# MCS4-2.net
KiCad netlist of a schematic drawn in Altium Designer
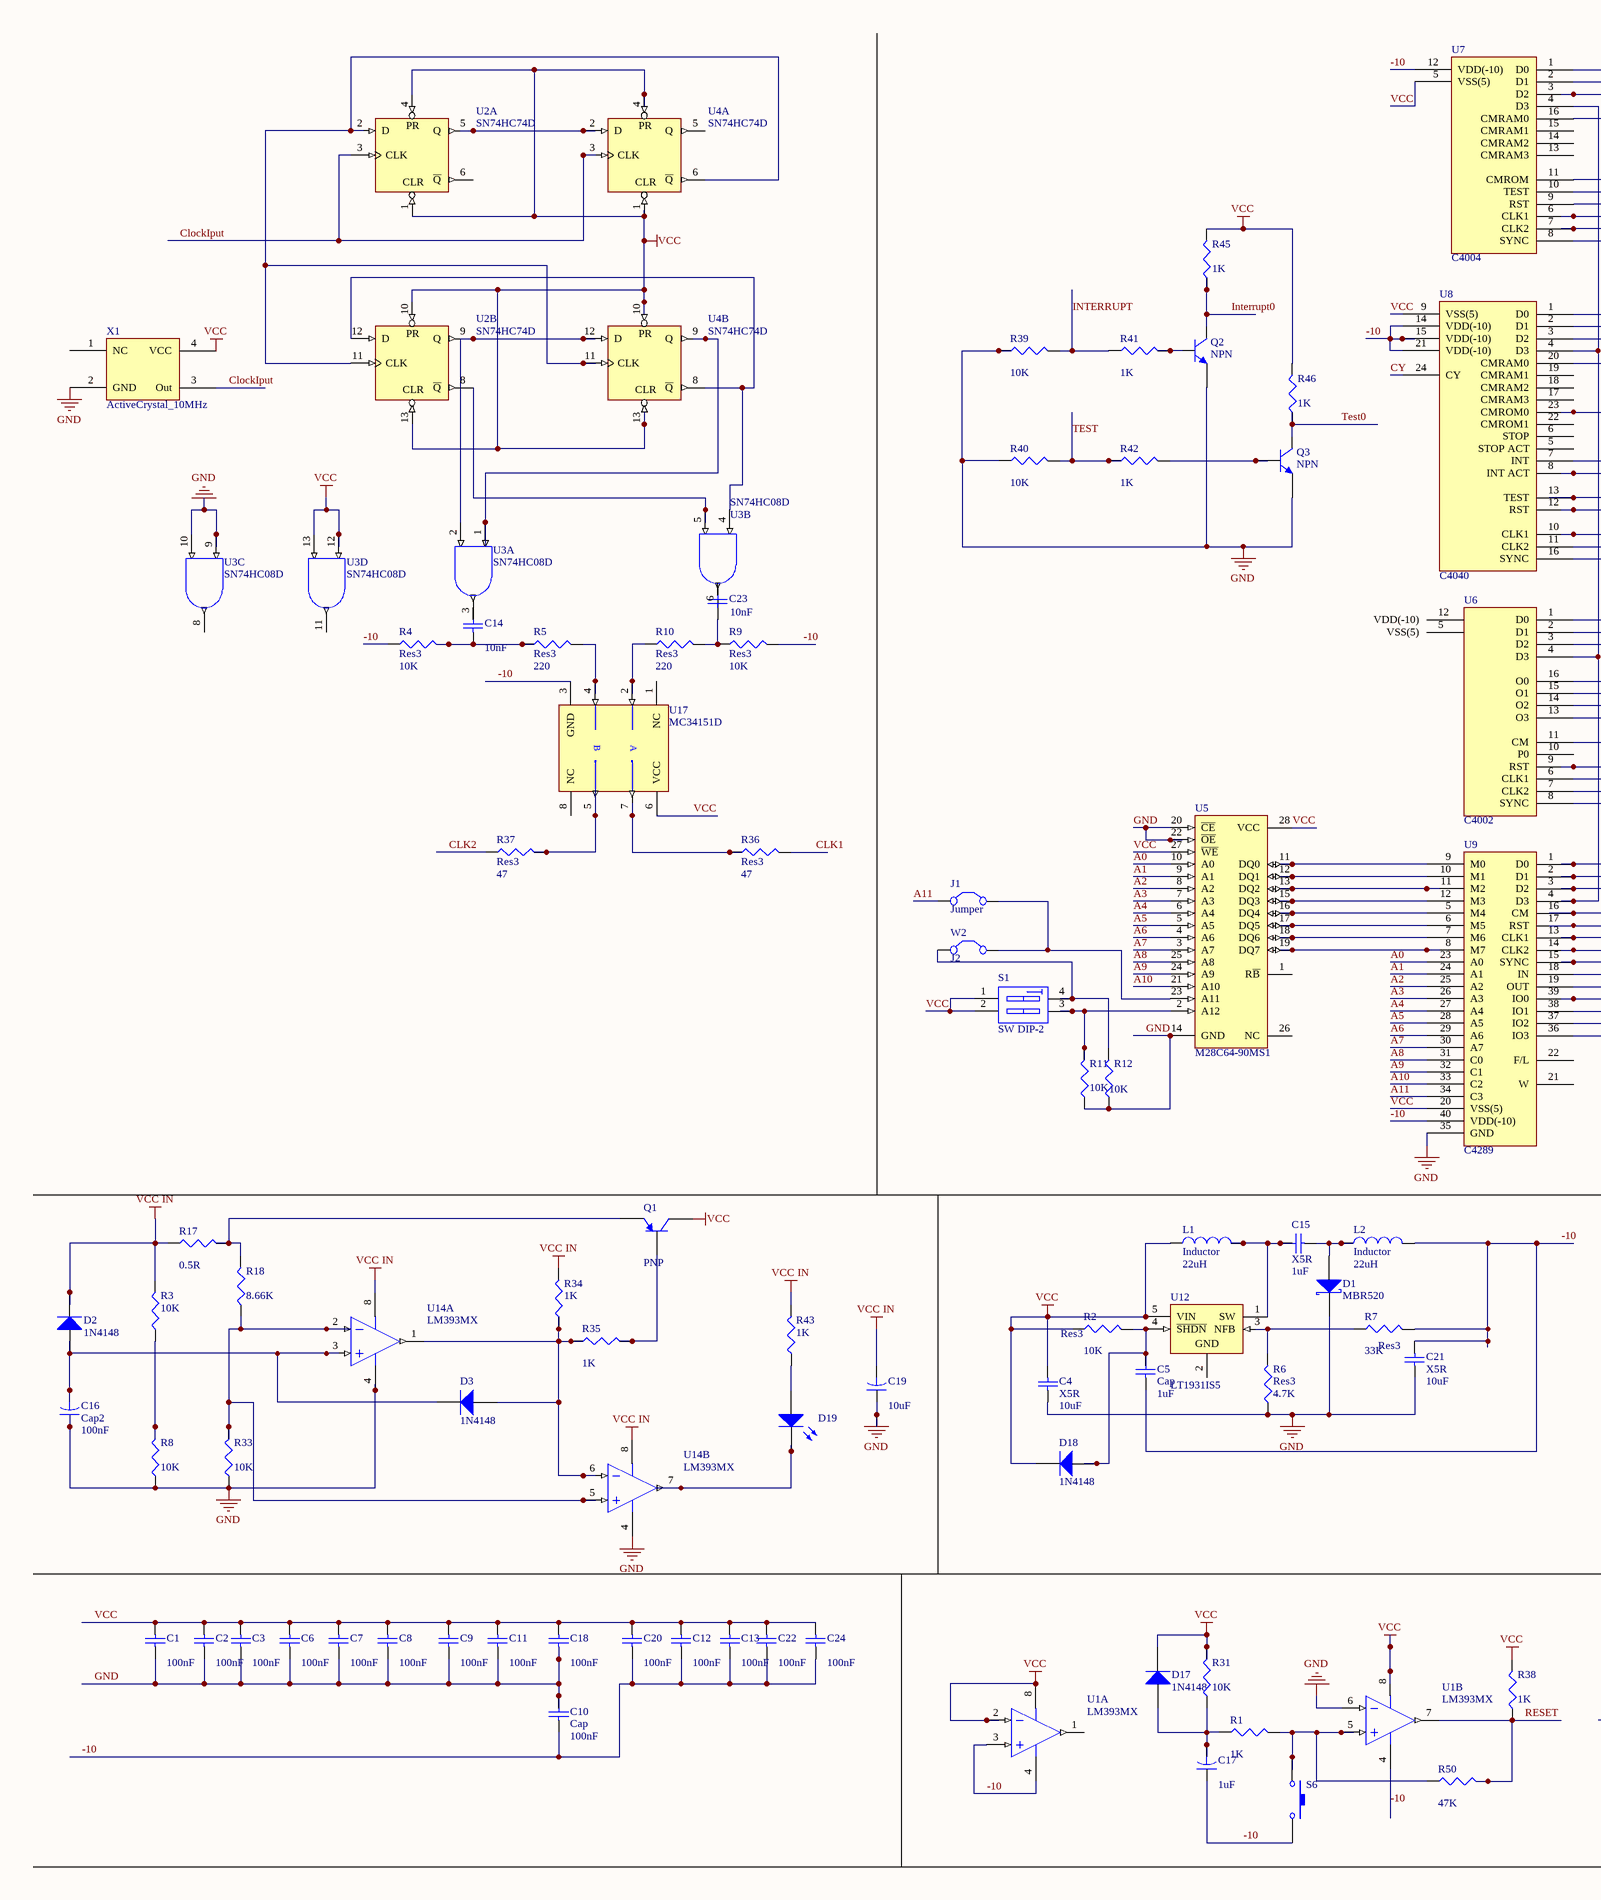
[diagram p0: MCS4-2.SchDoc, left]
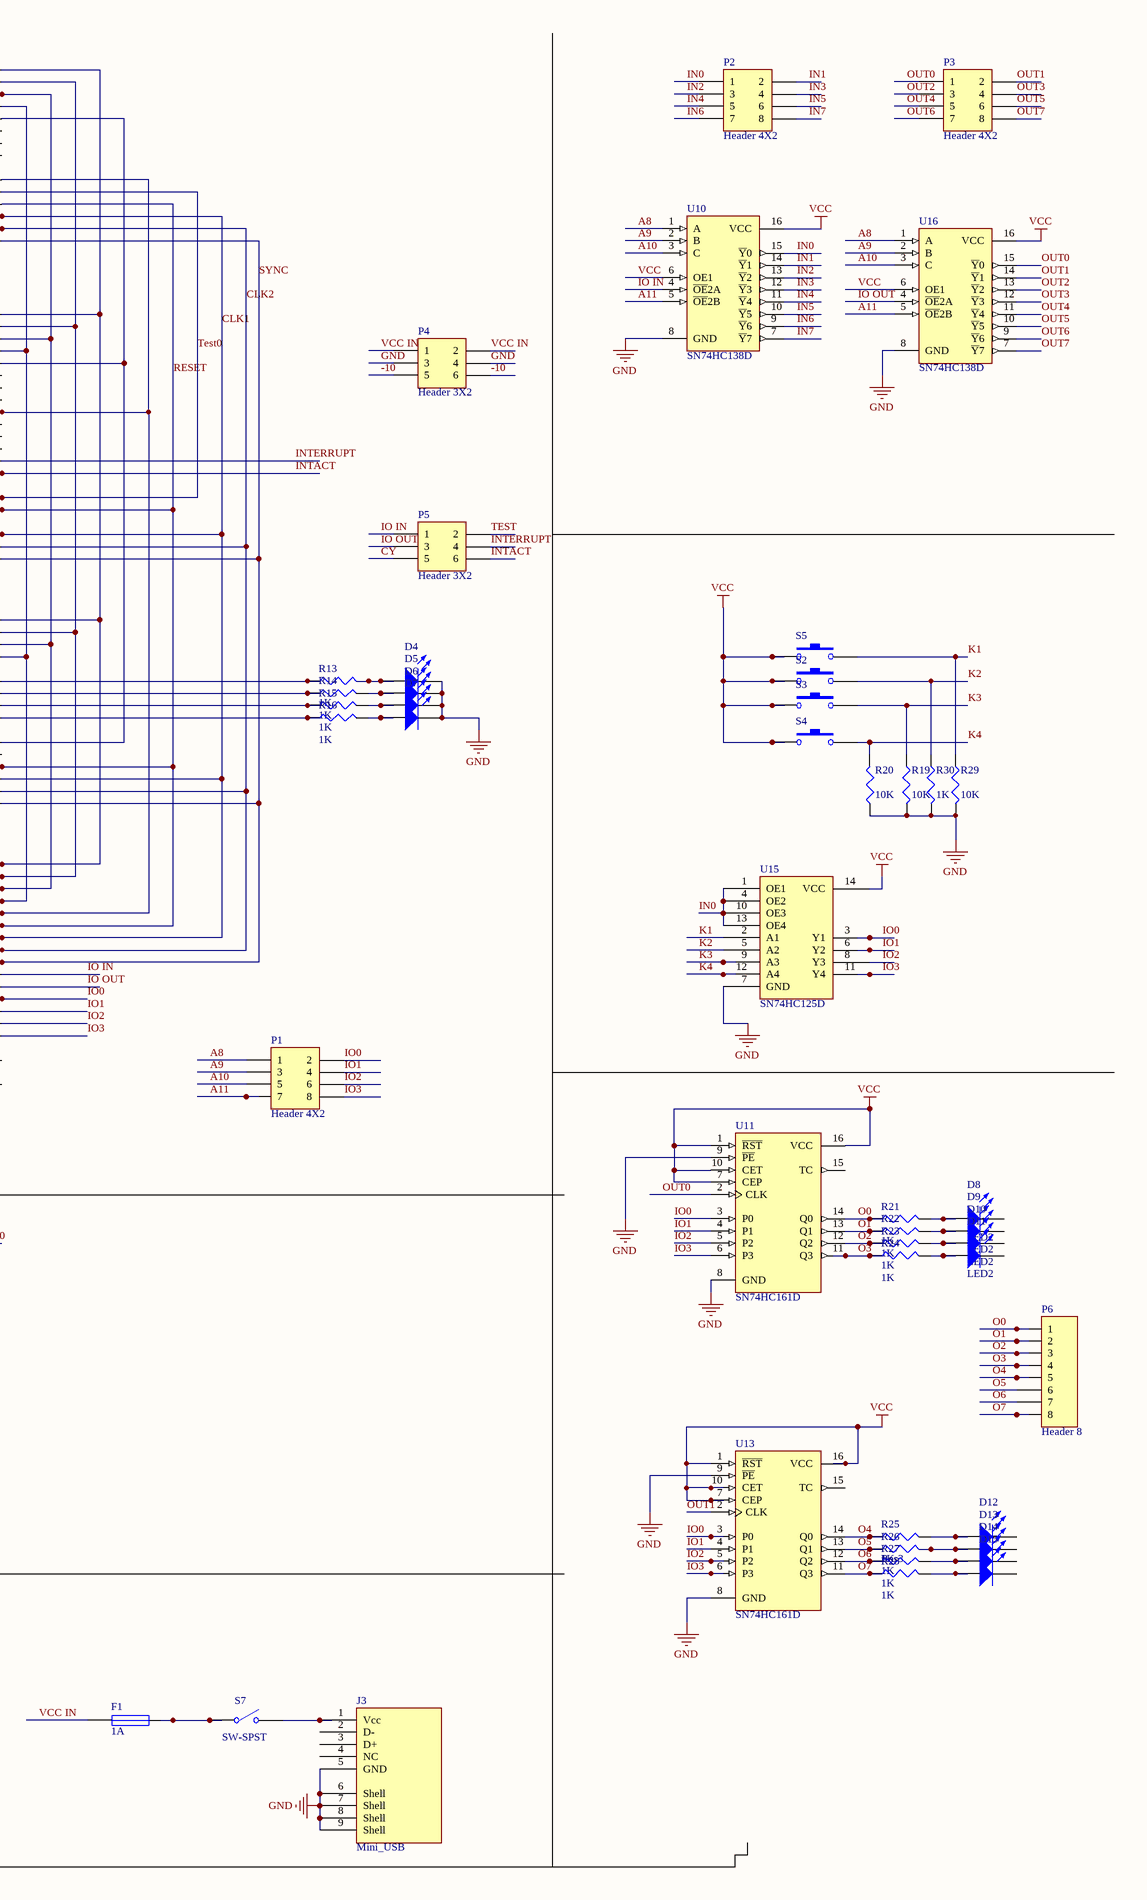
[diagram p1: MCS4-2.SchDoc, right]

(export (version "E")
  (design (tool "Eeschema 10.0.6"))
  (components
    (comp (ref "C1")
      (value "100nF")
      (footprint "RAD-0.3")
      (description "Capacitor")
      (fields (field (name "Comment") "Cap") (field (name "PUBLISHER") "Altium Limited"))
      (libsource (lib "Miscellaneous Devices") (part "Cap"))
    )
    (comp (ref "C2")
      (value "100nF")
      (footprint "RAD-0.3")
      (description "Capacitor")
      (fields (field (name "Comment") "Cap") (field (name "PUBLISHER") "Altium Limited"))
      (libsource (lib "Miscellaneous Devices") (part "Cap"))
    )
    (comp (ref "C3")
      (value "100nF")
      (footprint "RAD-0.3")
      (description "Capacitor")
      (fields (field (name "Comment") "Cap") (field (name "PUBLISHER") "Altium Limited"))
      (libsource (lib "Miscellaneous Devices") (part "Cap"))
    )
    (comp (ref "C4")
      (value "X5R")
      (footprint "RAD-0.3")
      (description "Capacitor")
      (fields (field (name "ALTIUM_VALUE") "10uF") (field (name "PUBLISHER") "Altium Limited"))
      (libsource (lib "Miscellaneous Devices") (part "Cap"))
    )
    (comp (ref "C5")
      (value "Cap")
      (footprint "RAD-0.3")
      (description "Capacitor")
      (fields (field (name "ALTIUM_VALUE") "1uF") (field (name "PUBLISHER") "Altium Limited"))
      (libsource (lib "Miscellaneous Devices") (part "Cap"))
    )
    (comp (ref "C6")
      (value "100nF")
      (footprint "RAD-0.3")
      (description "Capacitor")
      (fields (field (name "Comment") "Cap") (field (name "PUBLISHER") "Altium Limited"))
      (libsource (lib "Miscellaneous Devices") (part "Cap"))
    )
    (comp (ref "C7")
      (value "100nF")
      (footprint "RAD-0.3")
      (description "Capacitor")
      (fields (field (name "Comment") "Cap") (field (name "PUBLISHER") "Altium Limited"))
      (libsource (lib "Miscellaneous Devices") (part "Cap"))
    )
    (comp (ref "C8")
      (value "100nF")
      (footprint "RAD-0.3")
      (description "Capacitor")
      (fields (field (name "Comment") "Cap") (field (name "PUBLISHER") "Altium Limited"))
      (libsource (lib "Miscellaneous Devices") (part "Cap"))
    )
    (comp (ref "C9")
      (value "100nF")
      (footprint "RAD-0.3")
      (description "Capacitor")
      (fields (field (name "Comment") "Cap") (field (name "PUBLISHER") "Altium Limited"))
      (libsource (lib "Miscellaneous Devices") (part "Cap"))
    )
    (comp (ref "C10")
      (value "Cap")
      (footprint "RAD-0.3")
      (description "Capacitor")
      (fields (field (name "ALTIUM_VALUE") "100nF") (field (name "PUBLISHER") "Altium Limited"))
      (libsource (lib "Miscellaneous Devices") (part "Cap"))
    )
    (comp (ref "C11")
      (value "100nF")
      (footprint "RAD-0.3")
      (description "Capacitor")
      (fields (field (name "Comment") "Cap") (field (name "PUBLISHER") "Altium Limited"))
      (libsource (lib "Miscellaneous Devices") (part "Cap"))
    )
    (comp (ref "C12")
      (value "100nF")
      (footprint "RAD-0.3")
      (description "Capacitor")
      (fields (field (name "Comment") "Cap") (field (name "PUBLISHER") "Altium Limited"))
      (libsource (lib "Miscellaneous Devices") (part "Cap"))
    )
    (comp (ref "C13")
      (value "100nF")
      (footprint "RAD-0.3")
      (description "Capacitor")
      (fields (field (name "Comment") "Cap") (field (name "PUBLISHER") "Altium Limited"))
      (libsource (lib "Miscellaneous Devices") (part "Cap"))
    )
    (comp (ref "C14")
      (value "10nF")
      (footprint "RAD-0.3")
      (description "Capacitor")
      (fields (field (name "PUBLISHER") "Altium Limited"))
      (libsource (lib "Miscellaneous Devices") (part "Cap"))
    )
    (comp (ref "C15")
      (value "X5R")
      (footprint "RAD-0.3")
      (fields (field (name "ALTIUM_VALUE") "1uF") (field (name "PUBLISHER") "Altium Limited"))
      (libsource (lib "Miscellaneous Devices") (part "Cap"))
    )
    (comp (ref "C16")
      (value "Cap2")
      (footprint "CAPR5-4X5")
      (description "Capacitor")
      (fields (field (name "ALTIUM_VALUE") "100nF") (field (name "PUBLISHER") "Altium Limited"))
      (libsource (lib "Miscellaneous Devices") (part "Cap2"))
    )
    (comp (ref "C17")
      (value "1uF")
      (footprint "CAPR5-4X5")
      (description "Capacitor")
      (fields (field (name "Comment") "Cap2") (field (name "PUBLISHER") "Altium Limited"))
      (libsource (lib "Miscellaneous Devices") (part "Cap2"))
    )
    (comp (ref "C18")
      (value "100nF")
      (footprint "RAD-0.3")
      (description "Capacitor")
      (fields (field (name "Comment") "Cap") (field (name "PUBLISHER") "Altium Limited"))
      (libsource (lib "Miscellaneous Devices") (part "Cap"))
    )
    (comp (ref "C19")
      (value "10uF")
      (footprint "CAPR5-4X5")
      (description "Capacitor")
      (fields (field (name "Comment") "Cap2") (field (name "PUBLISHER") "Altium Limited"))
      (libsource (lib "Miscellaneous Devices") (part "Cap2"))
    )
    (comp (ref "C20")
      (value "100nF")
      (footprint "RAD-0.3")
      (description "Capacitor")
      (fields (field (name "Comment") "Cap") (field (name "PUBLISHER") "Altium Limited"))
      (libsource (lib "Miscellaneous Devices") (part "Cap"))
    )
    (comp (ref "C21")
      (value "X5R")
      (footprint "RAD-0.3")
      (description "Capacitor")
      (fields (field (name "ALTIUM_VALUE") "10uF") (field (name "PUBLISHER") "Altium Limited"))
      (libsource (lib "Miscellaneous Devices") (part "Cap"))
    )
    (comp (ref "C22")
      (value "100nF")
      (footprint "RAD-0.3")
      (description "Capacitor")
      (fields (field (name "Comment") "Cap") (field (name "PUBLISHER") "Altium Limited"))
      (libsource (lib "Miscellaneous Devices") (part "Cap"))
    )
    (comp (ref "C23")
      (value "10nF")
      (footprint "RAD-0.3")
      (description "Capacitor")
      (fields (field (name "Comment") "Cap") (field (name "PUBLISHER") "Altium Limited"))
      (libsource (lib "Miscellaneous Devices") (part "Cap"))
    )
    (comp (ref "C24")
      (value "100nF")
      (footprint "RAD-0.3")
      (description "Capacitor")
      (fields (field (name "Comment") "Cap") (field (name "PUBLISHER") "Altium Limited"))
      (libsource (lib "Miscellaneous Devices") (part "Cap"))
    )
    (comp (ref "D1")
      (value "MBR520")
      (footprint "SMB")
      (fields (field (name "PUBLISHER") "Altium Limited"))
      (libsource (lib "Miscellaneous Devices") (part "D Schottky"))
    )
    (comp (ref "D2")
      (value "1N4148")
      (footprint "DO-35")
      (description "High Conductance Fast Diode")
      (fields (field (name "PUBLISHER") "Altium Limited"))
      (libsource (lib "1N4148 FSC Discrete Diode") (part "1N4148"))
    )
    (comp (ref "D3")
      (value "1N4148")
      (footprint "DO-35")
      (description "High Conductance Fast Diode")
      (fields (field (name "PUBLISHER") "Altium Limited"))
      (libsource (lib "1N4148 FSC Discrete Diode") (part "1N4148"))
    )
    (comp (ref "D4")
      (value "LED2")
      (footprint "3.2X1.6X1.1")
      (description "Typical RED, GREEN, YELLOW, AMBER GaAs LED")
      (fields (field (name "PUBLISHER") "Altium Limited"))
      (libsource (lib "Miscellaneous Devices") (part "LED2"))
    )
    (comp (ref "D5")
      (value "LED2")
      (footprint "3.2X1.6X1.1")
      (description "Typical RED, GREEN, YELLOW, AMBER GaAs LED")
      (fields (field (name "PUBLISHER") "Altium Limited"))
      (libsource (lib "Miscellaneous Devices") (part "LED2"))
    )
    (comp (ref "D6")
      (value "LED2")
      (footprint "3.2X1.6X1.1")
      (description "Typical RED, GREEN, YELLOW, AMBER GaAs LED")
      (fields (field (name "PUBLISHER") "Altium Limited"))
      (libsource (lib "Miscellaneous Devices") (part "LED2"))
    )
    (comp (ref "D7")
      (value "LED2")
      (footprint "3.2X1.6X1.1")
      (description "Typical RED, GREEN, YELLOW, AMBER GaAs LED")
      (fields (field (name "PUBLISHER") "Altium Limited"))
      (libsource (lib "Miscellaneous Devices") (part "LED2"))
    )
    (comp (ref "D8")
      (value "LED2")
      (footprint "3.2X1.6X1.1")
      (description "Typical RED, GREEN, YELLOW, AMBER GaAs LED")
      (fields (field (name "PUBLISHER") "Altium Limited"))
      (libsource (lib "Miscellaneous Devices") (part "LED2"))
    )
    (comp (ref "D9")
      (value "LED2")
      (footprint "3.2X1.6X1.1")
      (description "Typical RED, GREEN, YELLOW, AMBER GaAs LED")
      (fields (field (name "PUBLISHER") "Altium Limited"))
      (libsource (lib "Miscellaneous Devices") (part "LED2"))
    )
    (comp (ref "D10")
      (value "LED2")
      (footprint "3.2X1.6X1.1")
      (description "Typical RED, GREEN, YELLOW, AMBER GaAs LED")
      (fields (field (name "PUBLISHER") "Altium Limited"))
      (libsource (lib "Miscellaneous Devices") (part "LED2"))
    )
    (comp (ref "D11")
      (value "LED2")
      (footprint "3.2X1.6X1.1")
      (description "Typical RED, GREEN, YELLOW, AMBER GaAs LED")
      (fields (field (name "PUBLISHER") "Altium Limited"))
      (libsource (lib "Miscellaneous Devices") (part "LED2"))
    )
    (comp (ref "D12")
      (value "LED2")
      (footprint "3.2X1.6X1.1")
      (description "Typical RED, GREEN, YELLOW, AMBER GaAs LED")
      (fields (field (name "PUBLISHER") "Altium Limited"))
      (libsource (lib "Miscellaneous Devices") (part "LED2"))
    )
    (comp (ref "D13")
      (value "LED2")
      (footprint "3.2X1.6X1.1")
      (description "Typical RED, GREEN, YELLOW, AMBER GaAs LED")
      (fields (field (name "PUBLISHER") "Altium Limited"))
      (libsource (lib "Miscellaneous Devices") (part "LED2"))
    )
    (comp (ref "D14")
      (value "LED2")
      (footprint "3.2X1.6X1.1")
      (description "Typical RED, GREEN, YELLOW, AMBER GaAs LED")
      (fields (field (name "PUBLISHER") "Altium Limited"))
      (libsource (lib "Miscellaneous Devices") (part "LED2"))
    )
    (comp (ref "D15")
      (value "LED2")
      (footprint "3.2X1.6X1.1")
      (description "Typical RED, GREEN, YELLOW, AMBER GaAs LED")
      (fields (field (name "PUBLISHER") "Altium Limited"))
      (libsource (lib "Miscellaneous Devices") (part "LED2"))
    )
    (comp (ref "D17")
      (value "1N4148")
      (footprint "DO-35")
      (description "High Conductance Fast Diode")
      (fields (field (name "PUBLISHER") "Altium Limited"))
      (libsource (lib "1N4148 FSC Discrete Diode") (part "1N4148"))
    )
    (comp (ref "D18")
      (value "1N4148")
      (footprint "DO-35")
      (description "High Conductance Fast Diode")
      (fields (field (name "PUBLISHER") "Altium Limited"))
      (libsource (lib "1N4148 FSC Discrete Diode") (part "1N4148"))
    )
    (comp (ref "D19")
      (value "LED2")
      (footprint "3.2X1.6X1.1")
      (description "Typical RED, GREEN, YELLOW, AMBER GaAs LED")
      (fields (field (name "PUBLISHER") "Altium Limited"))
      (libsource (lib "Miscellaneous Devices") (part "LED2"))
    )
    (comp (ref "F1")
      (value "1A")
      (footprint "PIN-W2/E2.8")
      (fields (field (name "PUBLISHER") "Altium Limited"))
      (libsource (lib "Miscellaneous Devices") (part "Fuse 1"))
    )
    (comp (ref "J1")
      (value "Jumper")
      (footprint "RAD-0.2")
      (description "Jumper Wire")
      (fields (field (name "PUBLISHER") "Altium Limited"))
      (libsource (lib "Miscellaneous Devices") (part "Jumper"))
    )
    (comp (ref "J3") (value "Mini_USB") (footprint "Mini_USB") (libsource (lib "usbmin2") (part "Mini_USB")))
    (comp (ref "L1")
      (value "Inductor")
      (footprint "INDP110102X50N")
      (fields (field (name "ALTIUM_VALUE") "22uH") (field (name "PUBLISHER") "Altium Limited"))
      (libsource (lib "Miscellaneous Devices") (part "Inductor"))
    )
    (comp (ref "L2")
      (value "Inductor")
      (footprint "INDP110102X50N")
      (fields (field (name "ALTIUM_VALUE") "22uH") (field (name "PUBLISHER") "Altium Limited"))
      (libsource (lib "Miscellaneous Devices") (part "Inductor"))
    )
    (comp (ref "P1")
      (value "Header 4X2")
      (footprint "HDR2X4")
      (description "Header, 4-Pin, Dual row")
      (fields (field (name "PUBLISHER") "Altium Limited"))
      (libsource (lib "Miscellaneous Connectors") (part "Header 4X2"))
    )
    (comp (ref "P2")
      (value "Header 4X2")
      (footprint "HDR2X4")
      (description "Header, 4-Pin, Dual row")
      (fields (field (name "PUBLISHER") "Altium Limited"))
      (libsource (lib "Miscellaneous Connectors") (part "Header 4X2"))
    )
    (comp (ref "P3")
      (value "Header 4X2")
      (footprint "HDR2X4")
      (description "Header, 4-Pin, Dual row")
      (fields (field (name "PUBLISHER") "Altium Limited"))
      (libsource (lib "Miscellaneous Connectors") (part "Header 4X2"))
    )
    (comp (ref "P4")
      (value "Header 3X2")
      (footprint "HDR2X3")
      (description "Header, 3-Pin, Dual row")
      (fields (field (name "PUBLISHER") "Altium Limited"))
      (libsource (lib "Miscellaneous Connectors") (part "Header 3X2"))
    )
    (comp (ref "P5")
      (value "Header 3X2")
      (footprint "HDR2X3")
      (description "Header, 3-Pin, Dual row")
      (fields (field (name "PUBLISHER") "Altium Limited"))
      (libsource (lib "Miscellaneous Connectors") (part "Header 3X2"))
    )
    (comp (ref "P6")
      (value "Header 8")
      (footprint "HDR1X8")
      (description "Header, 8-Pin")
      (fields (field (name "PUBLISHER") "Altium Limited"))
      (libsource (lib "Miscellaneous Connectors") (part "Header 8"))
    )
    (comp (ref "Q1")
      (value "PNP")
      (footprint "SOT-23B_N")
      (description "PNP Bipolar Transistor")
      (fields (field (name "PUBLISHER") "Altium Limited"))
      (libsource (lib "Miscellaneous Devices") (part "PNP"))
    )
    (comp (ref "Q2")
      (value "NPN")
      (footprint "TO-226-AA")
      (description "NPN Bipolar Transistor")
      (fields (field (name "PUBLISHER") "Altium Limited"))
      (libsource (lib "Miscellaneous Devices") (part "NPN"))
    )
    (comp (ref "Q3")
      (value "NPN")
      (footprint "TO-226-AA")
      (description "NPN Bipolar Transistor")
      (fields (field (name "PUBLISHER") "Altium Limited"))
      (libsource (lib "Miscellaneous Devices") (part "NPN"))
    )
    (comp (ref "R1")
      (value "1K")
      (footprint "J1-0603")
      (description "Resistor")
      (fields (field (name "Comment") "Res3") (field (name "PUBLISHER") "Altium Limited"))
      (libsource (lib "Miscellaneous Devices") (part "Res3"))
    )
    (comp (ref "R2")
      (value "Res3")
      (footprint "J1-0603")
      (description "Resistor")
      (fields (field (name "ALTIUM_VALUE") "10K") (field (name "PUBLISHER") "Altium Limited"))
      (libsource (lib "Miscellaneous Devices") (part "Res3"))
    )
    (comp (ref "R3")
      (value "10K")
      (footprint "J1-0603")
      (description "Resistor")
      (fields (field (name "Comment") "Res3") (field (name "PUBLISHER") "Altium Limited"))
      (libsource (lib "Miscellaneous Devices") (part "Res3"))
    )
    (comp (ref "R4")
      (value "Res3")
      (footprint "J1-0603")
      (description "Resistor")
      (fields (field (name "ALTIUM_VALUE") "10K") (field (name "PUBLISHER") "Altium Limited"))
      (libsource (lib "Miscellaneous Devices") (part "Res3"))
    )
    (comp (ref "R5")
      (value "Res3")
      (footprint "J1-0603")
      (description "Resistor")
      (fields (field (name "ALTIUM_VALUE") "220") (field (name "PUBLISHER") "Altium Limited"))
      (libsource (lib "Miscellaneous Devices") (part "Res3"))
    )
    (comp (ref "R6")
      (value "Res3")
      (footprint "J1-0603")
      (description "Resistor")
      (fields (field (name "ALTIUM_VALUE") "4.7K") (field (name "PUBLISHER") "Altium Limited"))
      (libsource (lib "Miscellaneous Devices") (part "Res3"))
    )
    (comp (ref "R7")
      (value "Res3")
      (footprint "J1-0603")
      (description "Resistor")
      (fields (field (name "ALTIUM_VALUE") "33K") (field (name "PUBLISHER") "Altium Limited"))
      (libsource (lib "Miscellaneous Devices") (part "Res3"))
    )
    (comp (ref "R8")
      (value "10K")
      (footprint "J1-0603")
      (description "Resistor")
      (fields (field (name "Comment") "Res3") (field (name "PUBLISHER") "Altium Limited"))
      (libsource (lib "Miscellaneous Devices") (part "Res3"))
    )
    (comp (ref "R9")
      (value "Res3")
      (footprint "J1-0603")
      (description "Resistor")
      (fields (field (name "ALTIUM_VALUE") "10K") (field (name "PUBLISHER") "Altium Limited"))
      (libsource (lib "Miscellaneous Devices") (part "Res3"))
    )
    (comp (ref "R10")
      (value "Res3")
      (footprint "J1-0603")
      (description "Resistor")
      (fields (field (name "ALTIUM_VALUE") "220") (field (name "PUBLISHER") "Altium Limited"))
      (libsource (lib "Miscellaneous Devices") (part "Res3"))
    )
    (comp (ref "R11")
      (value "10K")
      (footprint "J1-0603")
      (description "Resistor")
      (fields (field (name "Comment") "Res3") (field (name "PUBLISHER") "Altium Limited"))
      (libsource (lib "Miscellaneous Devices") (part "Res3"))
    )
    (comp (ref "R12")
      (value "10K")
      (footprint "J1-0603")
      (description "Resistor")
      (fields (field (name "Comment") "Res3") (field (name "PUBLISHER") "Altium Limited"))
      (libsource (lib "Miscellaneous Devices") (part "Res3"))
    )
    (comp (ref "R13")
      (value "1K")
      (footprint "J1-0603")
      (description "Resistor")
      (fields (field (name "Comment") "Res3") (field (name "PUBLISHER") "Altium Limited"))
      (libsource (lib "Miscellaneous Devices") (part "Res3"))
    )
    (comp (ref "R14")
      (value "1K")
      (footprint "J1-0603")
      (description "Resistor")
      (fields (field (name "Comment") "Res3") (field (name "PUBLISHER") "Altium Limited"))
      (libsource (lib "Miscellaneous Devices") (part "Res3"))
    )
    (comp (ref "R15")
      (value "1K")
      (footprint "J1-0603")
      (description "Resistor")
      (fields (field (name "Comment") "Res3") (field (name "PUBLISHER") "Altium Limited"))
      (libsource (lib "Miscellaneous Devices") (part "Res3"))
    )
    (comp (ref "R16")
      (value "1K")
      (footprint "J1-0603")
      (description "Resistor")
      (fields (field (name "Comment") "Res3") (field (name "PUBLISHER") "Altium Limited"))
      (libsource (lib "Miscellaneous Devices") (part "Res3"))
    )
    (comp (ref "R17")
      (value "0.5R")
      (footprint "J1-0603")
      (description "Resistor")
      (fields (field (name "Comment") "Res3") (field (name "PUBLISHER") "Altium Limited"))
      (libsource (lib "Miscellaneous Devices") (part "Res3"))
    )
    (comp (ref "R18")
      (value "8.66K")
      (footprint "J1-0603")
      (description "Resistor")
      (fields (field (name "Comment") "Res3") (field (name "PUBLISHER") "Altium Limited"))
      (libsource (lib "Miscellaneous Devices") (part "Res3"))
    )
    (comp (ref "R19")
      (value "10K")
      (footprint "J1-0603")
      (description "Resistor")
      (fields (field (name "Comment") "Res3") (field (name "PUBLISHER") "Altium Limited"))
      (libsource (lib "Miscellaneous Devices") (part "Res3"))
    )
    (comp (ref "R20")
      (value "10K")
      (footprint "J1-0603")
      (description "Resistor")
      (fields (field (name "Comment") "Res3") (field (name "PUBLISHER") "Altium Limited"))
      (libsource (lib "Miscellaneous Devices") (part "Res3"))
    )
    (comp (ref "R21")
      (value "1K")
      (footprint "J1-0603")
      (description "Resistor")
      (fields (field (name "Comment") "Res3") (field (name "PUBLISHER") "Altium Limited"))
      (libsource (lib "Miscellaneous Devices") (part "Res3"))
    )
    (comp (ref "R22")
      (value "1K")
      (footprint "J1-0603")
      (description "Resistor")
      (fields (field (name "Comment") "Res3") (field (name "PUBLISHER") "Altium Limited"))
      (libsource (lib "Miscellaneous Devices") (part "Res3"))
    )
    (comp (ref "R23")
      (value "1K")
      (footprint "J1-0603")
      (description "Resistor")
      (fields (field (name "Comment") "Res3") (field (name "PUBLISHER") "Altium Limited"))
      (libsource (lib "Miscellaneous Devices") (part "Res3"))
    )
    (comp (ref "R24")
      (value "1K")
      (footprint "J1-0603")
      (description "Resistor")
      (fields (field (name "Comment") "Res3") (field (name "PUBLISHER") "Altium Limited"))
      (libsource (lib "Miscellaneous Devices") (part "Res3"))
    )
    (comp (ref "R25")
      (value "1K")
      (footprint "J1-0603")
      (description "Resistor")
      (fields (field (name "Comment") "Res3") (field (name "PUBLISHER") "Altium Limited"))
      (libsource (lib "Miscellaneous Devices") (part "Res3"))
    )
    (comp (ref "R26")
      (value "Res3")
      (footprint "J1-0603")
      (description "Resistor")
      (fields (field (name "ALTIUM_VALUE") "1K") (field (name "PUBLISHER") "Altium Limited"))
      (libsource (lib "Miscellaneous Devices") (part "Res3"))
    )
    (comp (ref "R27")
      (value "1K")
      (footprint "J1-0603")
      (description "Resistor")
      (fields (field (name "Comment") "Res3") (field (name "PUBLISHER") "Altium Limited"))
      (libsource (lib "Miscellaneous Devices") (part "Res3"))
    )
    (comp (ref "R28")
      (value "1K")
      (footprint "J1-0603")
      (description "Resistor")
      (fields (field (name "Comment") "Res3") (field (name "PUBLISHER") "Altium Limited"))
      (libsource (lib "Miscellaneous Devices") (part "Res3"))
    )
    (comp (ref "R29")
      (value "10K")
      (footprint "J1-0603")
      (description "Resistor")
      (fields (field (name "Comment") "Res3") (field (name "PUBLISHER") "Altium Limited"))
      (libsource (lib "Miscellaneous Devices") (part "Res3"))
    )
    (comp (ref "R30")
      (value "1K")
      (footprint "J1-0603")
      (description "Resistor")
      (fields (field (name "Comment") "Res3") (field (name "PUBLISHER") "Altium Limited"))
      (libsource (lib "Miscellaneous Devices") (part "Res3"))
    )
    (comp (ref "R31")
      (value "10K")
      (footprint "J1-0603")
      (description "Resistor")
      (fields (field (name "Comment") "Res3") (field (name "PUBLISHER") "Altium Limited"))
      (libsource (lib "Miscellaneous Devices") (part "Res3"))
    )
    (comp (ref "R33")
      (value "10K")
      (footprint "J1-0603")
      (description "Resistor")
      (fields (field (name "Comment") "Res3") (field (name "PUBLISHER") "Altium Limited"))
      (libsource (lib "Miscellaneous Devices") (part "Res3"))
    )
    (comp (ref "R34")
      (value "1K")
      (footprint "J1-0603")
      (description "Resistor")
      (fields (field (name "Comment") "Res3") (field (name "PUBLISHER") "Altium Limited"))
      (libsource (lib "Miscellaneous Devices") (part "Res3"))
    )
    (comp (ref "R35")
      (value "1K")
      (footprint "J1-0603")
      (description "Resistor")
      (fields (field (name "Comment") "Res3") (field (name "PUBLISHER") "Altium Limited"))
      (libsource (lib "Miscellaneous Devices") (part "Res3"))
    )
    (comp (ref "R36")
      (value "Res3")
      (footprint "J1-0603")
      (description "Resistor")
      (fields (field (name "ALTIUM_VALUE") "47") (field (name "PUBLISHER") "Altium Limited"))
      (libsource (lib "Miscellaneous Devices") (part "Res3"))
    )
    (comp (ref "R37")
      (value "Res3")
      (footprint "J1-0603")
      (description "Resistor")
      (fields (field (name "ALTIUM_VALUE") "47") (field (name "PUBLISHER") "Altium Limited"))
      (libsource (lib "Miscellaneous Devices") (part "Res3"))
    )
    (comp (ref "R38")
      (value "1K")
      (footprint "J1-0603")
      (description "Resistor")
      (fields (field (name "Comment") "Res3") (field (name "PUBLISHER") "Altium Limited"))
      (libsource (lib "Miscellaneous Devices") (part "Res3"))
    )
    (comp (ref "R39")
      (value "10K")
      (footprint "J1-0603")
      (description "Resistor")
      (fields (field (name "Comment") "Res3") (field (name "PUBLISHER") "Altium Limited"))
      (libsource (lib "Miscellaneous Devices") (part "Res3"))
    )
    (comp (ref "R40")
      (value "10K")
      (footprint "J1-0603")
      (description "Resistor")
      (fields (field (name "Comment") "Res3") (field (name "PUBLISHER") "Altium Limited"))
      (libsource (lib "Miscellaneous Devices") (part "Res3"))
    )
    (comp (ref "R41")
      (value "1K")
      (footprint "J1-0603")
      (description "Resistor")
      (fields (field (name "Comment") "Res3") (field (name "PUBLISHER") "Altium Limited"))
      (libsource (lib "Miscellaneous Devices") (part "Res3"))
    )
    (comp (ref "R42")
      (value "1K")
      (footprint "J1-0603")
      (description "Resistor")
      (fields (field (name "Comment") "Res3") (field (name "PUBLISHER") "Altium Limited"))
      (libsource (lib "Miscellaneous Devices") (part "Res3"))
    )
    (comp (ref "R43")
      (value "1K")
      (footprint "J1-0603")
      (description "Resistor")
      (fields (field (name "Comment") "Res3") (field (name "PUBLISHER") "Altium Limited"))
      (libsource (lib "Miscellaneous Devices") (part "Res3"))
    )
    (comp (ref "R45")
      (value "1K")
      (footprint "J1-0603")
      (description "Resistor")
      (fields (field (name "Comment") "Res3") (field (name "PUBLISHER") "Altium Limited"))
      (libsource (lib "Miscellaneous Devices") (part "Res3"))
    )
    (comp (ref "R46")
      (value "1K")
      (footprint "J1-0603")
      (description "Resistor")
      (fields (field (name "Comment") "Res3") (field (name "PUBLISHER") "Altium Limited"))
      (libsource (lib "Miscellaneous Devices") (part "Res3"))
    )
    (comp (ref "R50")
      (value "47K")
      (footprint "J1-0603")
      (description "Resistor")
      (fields (field (name "Comment") "Res3") (field (name "PUBLISHER") "Altium Limited"))
      (libsource (lib "Miscellaneous Devices") (part "Res3"))
    )
    (comp (ref "S1")
      (value "SW DIP-2")
      (footprint "DIP-4")
      (description "DIP Switch, 2 Position, SPST")
      (fields (field (name "PUBLISHER") "Altium Limited"))
      (libsource (lib "Miscellaneous Devices") (part "SW DIP-2"))
    )
    (comp (ref "S2")
      (value "SW-PB")
      (footprint "SPST-2")
      (description "Switch")
      (fields (field (name "PUBLISHER") "Altium Limited"))
      (libsource (lib "Miscellaneous Devices") (part "SW-PB"))
    )
    (comp (ref "S3")
      (value "SW-PB")
      (footprint "SPST-2")
      (description "Switch")
      (fields (field (name "PUBLISHER") "Altium Limited"))
      (libsource (lib "Miscellaneous Devices") (part "SW-PB"))
    )
    (comp (ref "S4")
      (value "SW-PB")
      (footprint "SPST-2")
      (description "Switch")
      (fields (field (name "PUBLISHER") "Altium Limited"))
      (libsource (lib "Miscellaneous Devices") (part "SW-PB"))
    )
    (comp (ref "S5")
      (value "SW-PB")
      (footprint "SPST-2")
      (description "Switch")
      (fields (field (name "PUBLISHER") "Altium Limited"))
      (libsource (lib "Miscellaneous Devices") (part "SW-PB"))
    )
    (comp (ref "S6")
      (value "SW-PB")
      (footprint "SPST-2")
      (description "Switch")
      (fields (field (name "PUBLISHER") "Altium Limited"))
      (libsource (lib "Miscellaneous Devices") (part "SW-PB"))
    )
    (comp (ref "S7")
      (value "SW-SPST")
      (footprint "SPST-2")
      (description "Single-Pole, Single-Throw Switch")
      (fields (field (name "PUBLISHER") "Altium Limited"))
      (libsource (lib "Miscellaneous Devices") (part "SW-SPST"))
    )
    (comp (ref "U1")
      (value "LM393MX")
      (footprint "M08A_N")
      (description "Low Power Low Offset Voltage Dual Comparator")
      (fields
        (field (name "MANUFACTURER") "National Semiconductor")
        (field (name "DIGIKEYPARTNUMBER") "LM393MXCT-ND")
        (field (name "PUBLISHER") "Altium Limited")
      )
      (libsource (lib "LM393MX NSC Comparator") (part "LM393MX"))
    )
    (comp (ref "U2")
      (value "SN74HC74D")
      (footprint "D014_N")
      (description "Dual D-Type Positive-Edge-Triggered Flip-Flop with Clear and Preset")
      (fields (field (name "PUBLISHER") "Altium Limited"))
      (libsource (lib "SN74HC74DTI Logic Flip-Flop") (part "SN74HC74D"))
    )
    (comp (ref "U3")
      (value "SN74HC08D")
      (footprint "D014_N")
      (description "Quadruple 2-Input Positive-AND Gate")
      (fields (field (name "PUBLISHER") "Altium Limited"))
      (libsource (lib "SN74HC08DTI Logic Gate 2") (part "SN74HC08D"))
    )
    (comp (ref "U4")
      (value "SN74HC74D")
      (footprint "D014_N")
      (description "Dual D-Type Positive-Edge-Triggered Flip-Flop with Clear and Preset")
      (fields (field (name "PUBLISHER") "Altium Limited"))
      (libsource (lib "SN74HC74DTI Logic Flip-Flop") (part "SN74HC74D"))
    )
    (comp (ref "U5")
      (value "M28C64-90MS1")
      (footprint "SO28_N")
      (description "64 Kbit (8K x 8) Parallel EEPROM with Software Data Protection")
      (fields (field (name "PUBLISHER") "Altium Limited"))
      (libsource (lib "M28C64 ST Memory EEPROM Parallel") (part "M28C64-90MS1"))
    )
    (comp (ref "U6") (value "C4002") (footprint "P4002") (libsource (lib "C4002") (part "C4002")))
    (comp (ref "U7") (value "C4004") (footprint "P4004") (libsource (lib "C4004") (part "C4004")))
    (comp (ref "U8") (value "C4040") (footprint "P4040") (libsource (lib "C4040") (part "C4040")))
    (comp (ref "U9") (value "C4289") (footprint "C4289") (libsource (lib "C4289") (part "C4289")))
    (comp (ref "U10")
      (value "SN74HC138D")
      (footprint "D016_N")
      (description "3-Line to 8-Line Decoder / Demultiplexer")
      (fields (field (name "PUBLISHER") "Altium Limited"))
      (libsource (lib "SN74HC138DTI Logic Decoder Demux") (part "SN74HC138D"))
    )
    (comp (ref "U11")
      (value "SN74HC161D")
      (footprint "D016_N")
      (description "4-Bit Synchronous Binary Counter")
      (fields (field (name "PUBLISHER") "Altium Limited"))
      (libsource (lib "SN74HC161DTI Logic Counter") (part "SN74HC161D"))
    )
    (comp (ref "U12")
      (value "LT1931IS5")
      (footprint "S5-T_N")
      (description "1.2MHz Inverting Current Mode DC/DC Converter")
      (fields (field (name "PUBLISHER") "Altium Limited"))
      (libsource (lib "LT1931IS5LT Power Mgt DC-DC Converter") (part "LT1931IS5"))
    )
    (comp (ref "U13")
      (value "SN74HC161D")
      (footprint "D016_N")
      (description "4-Bit Synchronous Binary Counter")
      (fields (field (name "PUBLISHER") "Altium Limited"))
      (libsource (lib "SN74HC161DTI Logic Counter") (part "SN74HC161D"))
    )
    (comp (ref "U14")
      (value "LM393MX")
      (footprint "M08A_N")
      (description "Low Power Low Offset Voltage Dual Comparator")
      (fields
        (field (name "MANUFACTURER") "National Semiconductor")
        (field (name "DIGIKEYPARTNUMBER") "LM393MXCT-ND")
        (field (name "PUBLISHER") "Altium Limited")
      )
      (libsource (lib "LM393MX NSC Comparator") (part "LM393MX"))
    )
    (comp (ref "U15")
      (value "SN74HC125D")
      (footprint "SN74HC125D")
      (description "U15")
      (libsource (lib "SN74HC125D") (part "SN74HC125D"))
    )
    (comp (ref "U16")
      (value "SN74HC138D")
      (footprint "D016_N")
      (description "3-Line to 8-Line Decoder / Demultiplexer")
      (fields (field (name "PUBLISHER") "Altium Limited"))
      (libsource (lib "SN74HC138DTI Logic Decoder Demux") (part "SN74HC138D"))
    )
    (comp (ref "U17")
      (value "MC34151D")
      (footprint "751-06_N")
      (description "High Speed Dual MOSFET Driver")
      (fields (field (name "PUBLISHER") "Altium Limited"))
      (libsource (lib "MC3415DMotorola Interface MOSFET Driver") (part "MC34151D"))
    )
    (comp (ref "W2")
      (value "J2")
      (footprint "RAD-0.2")
      (description "Jumper Wire")
      (fields (field (name "PUBLISHER") "Altium Limited"))
      (libsource (lib "Miscellaneous Devices") (part "Jumper"))
    )
    (comp (ref "X1")
      (value "ActiveCrystal_10MHz")
      (footprint "ActiveCrystal_10MHz_7050")
      (libsource (lib "ActiveCrystal_10MHz") (part "ActiveCrystal_10MHz"))
    )
  )
  (nets
    (net (code "1") (name "/-10") (class "Default")
      (node (ref "C10") (pin "1") (pinfunction "1_1") (pintype "passive"))
      (node (ref "C12") (pin "1") (pinfunction "1_1") (pintype "passive"))
      (node (ref "C13") (pin "1") (pinfunction "1_1") (pintype "passive"))
      (node (ref "C17") (pin "1") (pinfunction "1_1") (pintype "passive"))
      (node (ref "C20") (pin "1") (pinfunction "1_1") (pintype "passive"))
      (node (ref "C21") (pin "2") (pinfunction "2_2") (pintype "passive"))
      (node (ref "C22") (pin "1") (pinfunction "1_1") (pintype "passive"))
      (node (ref "C24") (pin "1") (pinfunction "1_1") (pintype "passive"))
      (node (ref "C5") (pin "1") (pinfunction "1_1") (pintype "passive"))
      (node (ref "L2") (pin "2") (pinfunction "2_2") (pintype "passive"))
      (node (ref "P4") (pin "5") (pinfunction "5_5") (pintype "passive"))
      (node (ref "P4") (pin "6") (pinfunction "6_6") (pintype "passive"))
      (node (ref "R4") (pin "1") (pinfunction "1_1") (pintype "passive"))
      (node (ref "R7") (pin "2") (pinfunction "2_2") (pintype "passive"))
      (node (ref "R9") (pin "2") (pinfunction "2_2") (pintype "passive"))
      (node (ref "S6") (pin "2") (pinfunction "2_2") (pintype "passive"))
      (node (ref "U1") (pin "3") (pinfunction "INA+_3") (pintype "input"))
      (node (ref "U1") (pin "4") (pinfunction "GND_4") (pintype "power_in"))
      (node (ref "U17") (pin "3") (pinfunction "GND_3") (pintype "power_in"))
      (node (ref "U7") (pin "12") (pinfunction "VDD(-10)_12") (pintype "passive"))
      (node (ref "U8") (pin "14") (pinfunction "VDD(-10)_14") (pintype "passive"))
      (node (ref "U8") (pin "15") (pinfunction "VDD(-10)_15") (pintype "passive"))
      (node (ref "U8") (pin "21") (pinfunction "VDD(-10)_21") (pintype "passive"))
      (node (ref "U9") (pin "40") (pinfunction "VDD(-10)_40") (pintype "passive"))
    )
    (net (code "2") (name "/A0") (class "Default")
      (node (ref "U5") (pin "10") (pinfunction "A0_10") (pintype "input"))
      (node (ref "U9") (pin "23") (pinfunction "A0_23") (pintype "passive"))
    )
    (net (code "3") (name "/A1") (class "Default")
      (node (ref "U5") (pin "9") (pinfunction "A1_9") (pintype "input"))
      (node (ref "U9") (pin "24") (pinfunction "A1_24") (pintype "passive"))
    )
    (net (code "4") (name "/A2") (class "Default")
      (node (ref "U5") (pin "8") (pinfunction "A2_8") (pintype "input"))
      (node (ref "U9") (pin "25") (pinfunction "A2_25") (pintype "passive"))
    )
    (net (code "5") (name "/A3") (class "Default")
      (node (ref "U5") (pin "7") (pinfunction "A3_7") (pintype "input"))
      (node (ref "U9") (pin "26") (pinfunction "A3_26") (pintype "passive"))
    )
    (net (code "6") (name "/A4") (class "Default")
      (node (ref "U5") (pin "6") (pinfunction "A4_6") (pintype "input"))
      (node (ref "U9") (pin "27") (pinfunction "A4_27") (pintype "passive"))
    )
    (net (code "7") (name "/A5") (class "Default")
      (node (ref "U5") (pin "5") (pinfunction "A5_5") (pintype "input"))
      (node (ref "U9") (pin "28") (pinfunction "A5_28") (pintype "passive"))
    )
    (net (code "8") (name "/A6") (class "Default")
      (node (ref "U5") (pin "4") (pinfunction "A6_4") (pintype "input"))
      (node (ref "U9") (pin "29") (pinfunction "A6_29") (pintype "passive"))
    )
    (net (code "9") (name "/A7") (class "Default")
      (node (ref "U5") (pin "3") (pinfunction "A7_3") (pintype "input"))
      (node (ref "U9") (pin "30") (pinfunction "A7_30") (pintype "passive"))
    )
    (net (code "10") (name "/A8") (class "Default")
      (node (ref "P1") (pin "1") (pinfunction "1_1") (pintype "passive"))
      (node (ref "U10") (pin "1") (pinfunction "A_1") (pintype "input"))
      (node (ref "U16") (pin "1") (pinfunction "A_1") (pintype "input"))
      (node (ref "U5") (pin "25") (pinfunction "A8_25") (pintype "input"))
      (node (ref "U9") (pin "31") (pinfunction "C0_31") (pintype "passive"))
    )
    (net (code "11") (name "/A9") (class "Default")
      (node (ref "P1") (pin "3") (pinfunction "3_3") (pintype "passive"))
      (node (ref "U10") (pin "2") (pinfunction "B_2") (pintype "input"))
      (node (ref "U16") (pin "2") (pinfunction "B_2") (pintype "input"))
      (node (ref "U5") (pin "24") (pinfunction "A9_24") (pintype "input"))
      (node (ref "U9") (pin "32") (pinfunction "C1_32") (pintype "passive"))
    )
    (net (code "12") (name "/A10") (class "Default")
      (node (ref "P1") (pin "5") (pinfunction "5_5") (pintype "passive"))
      (node (ref "U10") (pin "3") (pinfunction "C_3") (pintype "input"))
      (node (ref "U16") (pin "3") (pinfunction "C_3") (pintype "input"))
      (node (ref "U5") (pin "21") (pinfunction "A10_21") (pintype "input"))
      (node (ref "U9") (pin "33") (pinfunction "C2_33") (pintype "passive"))
    )
    (net (code "13") (name "/A11") (class "Default")
      (node (ref "J1") (pin "1") (pinfunction "C1_1") (pintype "passive"))
      (node (ref "P1") (pin "7") (pinfunction "7_7") (pintype "passive"))
      (node (ref "U10") (pin "5") (pinfunction "~{OE}2B_5") (pintype "input"))
      (node (ref "U16") (pin "5") (pinfunction "~{OE}2B_5") (pintype "input"))
      (node (ref "U9") (pin "34") (pinfunction "C3_34") (pintype "passive"))
    )
    (net (code "14") (name "/CLK1") (class "Default")
      (node (ref "R36") (pin "2") (pinfunction "2_2") (pintype "passive"))
      (node (ref "U6") (pin "6") (pinfunction "CLK1_6") (pintype "passive"))
      (node (ref "U7") (pin "6") (pinfunction "CLK1_6") (pintype "passive"))
      (node (ref "U8") (pin "10") (pinfunction "CLK1_10") (pintype "passive"))
      (node (ref "U9") (pin "13") (pinfunction "CLK1_13") (pintype "passive"))
    )
    (net (code "15") (name "/CLK2") (class "Default")
      (node (ref "R37") (pin "1") (pinfunction "1_1") (pintype "passive"))
      (node (ref "U6") (pin "7") (pinfunction "CLK2_7") (pintype "passive"))
      (node (ref "U7") (pin "7") (pinfunction "CLK2_7") (pintype "passive"))
      (node (ref "U8") (pin "11") (pinfunction "CLK2_11") (pintype "passive"))
      (node (ref "U9") (pin "14") (pinfunction "CLK2_14") (pintype "passive"))
    )
    (net (code "16") (name "/CY") (class "Default")
      (node (ref "P5") (pin "5") (pinfunction "5_5") (pintype "passive"))
      (node (ref "U8") (pin "24") (pinfunction "CY_24") (pintype "passive"))
    )
    (net (code "17") (name "/ClockIput") (class "Default")
      (node (ref "U2") (pin "3") (pinfunction "CLK_3") (pintype "input"))
      (node (ref "U4") (pin "3") (pinfunction "CLK_3") (pintype "input"))
      (node (ref "X1") (pin "3") (pinfunction "Out_3") (pintype "passive"))
    )
    (net (code "18") (name "/IN0") (class "Default")
      (node (ref "P2") (pin "1") (pinfunction "1_1") (pintype "passive"))
      (node (ref "U10") (pin "15") (pinfunction "~{Y}0_15") (pintype "output"))
      (node (ref "U15") (pin "1") (pinfunction "OE1_1") (pintype "passive"))
      (node (ref "U15") (pin "10") (pinfunction "OE3_10") (pintype "passive"))
      (node (ref "U15") (pin "13") (pinfunction "OE4_13") (pintype "passive"))
      (node (ref "U15") (pin "4") (pinfunction "OE2_4") (pintype "passive"))
    )
    (net (code "19") (name "/IN1") (class "Default")
      (node (ref "P2") (pin "2") (pinfunction "2_2") (pintype "passive"))
      (node (ref "U10") (pin "14") (pinfunction "~{Y}1_14") (pintype "output"))
    )
    (net (code "20") (name "/IN2") (class "Default")
      (node (ref "P2") (pin "3") (pinfunction "3_3") (pintype "passive"))
      (node (ref "U10") (pin "13") (pinfunction "~{Y}2_13") (pintype "output"))
    )
    (net (code "21") (name "/IN3") (class "Default")
      (node (ref "P2") (pin "4") (pinfunction "4_4") (pintype "passive"))
      (node (ref "U10") (pin "12") (pinfunction "~{Y}3_12") (pintype "output"))
    )
    (net (code "22") (name "/IN4") (class "Default")
      (node (ref "P2") (pin "5") (pinfunction "5_5") (pintype "passive"))
      (node (ref "U10") (pin "11") (pinfunction "~{Y}4_11") (pintype "output"))
    )
    (net (code "23") (name "/IN5") (class "Default")
      (node (ref "P2") (pin "6") (pinfunction "6_6") (pintype "passive"))
      (node (ref "U10") (pin "10") (pinfunction "~{Y}5_10") (pintype "output"))
    )
    (net (code "24") (name "/IN6") (class "Default")
      (node (ref "P2") (pin "7") (pinfunction "7_7") (pintype "passive"))
      (node (ref "U10") (pin "9") (pinfunction "~{Y}6_9") (pintype "output"))
    )
    (net (code "25") (name "/IN7") (class "Default")
      (node (ref "P2") (pin "8") (pinfunction "8_8") (pintype "passive"))
      (node (ref "U10") (pin "7") (pinfunction "~{Y}7_7") (pintype "output"))
    )
    (net (code "26") (name "/INTACT") (class "Default")
      (node (ref "P5") (pin "6") (pinfunction "6_6") (pintype "passive"))
      (node (ref "U8") (pin "8") (pinfunction "INT_ACT_8") (pintype "passive"))
    )
    (net (code "27") (name "/INTERRUPT") (class "Default")
      (node (ref "P5") (pin "4") (pinfunction "4_4") (pintype "passive"))
      (node (ref "R39") (pin "2") (pinfunction "2_2") (pintype "passive"))
      (node (ref "R41") (pin "1") (pinfunction "1_1") (pintype "passive"))
      (node (ref "U8") (pin "7") (pinfunction "INT_7") (pintype "passive"))
    )
    (net (code "28") (name "/IO IN") (class "Default")
      (node (ref "P5") (pin "1") (pinfunction "1_1") (pintype "passive"))
      (node (ref "U10") (pin "4") (pinfunction "~{OE}2A_4") (pintype "input"))
      (node (ref "U9") (pin "18") (pinfunction "IN_18") (pintype "passive"))
    )
    (net (code "29") (name "/IO OUT") (class "Default")
      (node (ref "P5") (pin "3") (pinfunction "3_3") (pintype "passive"))
      (node (ref "U16") (pin "4") (pinfunction "~{OE}2A_4") (pintype "input"))
      (node (ref "U9") (pin "19") (pinfunction "OUT_19") (pintype "passive"))
    )
    (net (code "30") (name "/IO0") (class "Default")
      (node (ref "P1") (pin "2") (pinfunction "2_2") (pintype "passive"))
      (node (ref "U11") (pin "3") (pinfunction "P0_3") (pintype "input"))
      (node (ref "U13") (pin "3") (pinfunction "P0_3") (pintype "input"))
      (node (ref "U15") (pin "3") (pinfunction "Y1_3") (pintype "passive"))
      (node (ref "U9") (pin "39") (pinfunction "IO0_39") (pintype "passive"))
    )
    (net (code "31") (name "/IO1") (class "Default")
      (node (ref "P1") (pin "4") (pinfunction "4_4") (pintype "passive"))
      (node (ref "U11") (pin "4") (pinfunction "P1_4") (pintype "input"))
      (node (ref "U13") (pin "4") (pinfunction "P1_4") (pintype "input"))
      (node (ref "U15") (pin "6") (pinfunction "Y2_6") (pintype "passive"))
      (node (ref "U9") (pin "38") (pinfunction "IO1_38") (pintype "passive"))
    )
    (net (code "32") (name "/IO2") (class "Default")
      (node (ref "P1") (pin "6") (pinfunction "6_6") (pintype "passive"))
      (node (ref "U11") (pin "5") (pinfunction "P2_5") (pintype "input"))
      (node (ref "U13") (pin "5") (pinfunction "P2_5") (pintype "input"))
      (node (ref "U15") (pin "8") (pinfunction "Y3_8") (pintype "passive"))
      (node (ref "U9") (pin "37") (pinfunction "IO2_37") (pintype "passive"))
    )
    (net (code "33") (name "/IO3") (class "Default")
      (node (ref "P1") (pin "8") (pinfunction "8_8") (pintype "passive"))
      (node (ref "U11") (pin "6") (pinfunction "P3_6") (pintype "input"))
      (node (ref "U13") (pin "6") (pinfunction "P3_6") (pintype "input"))
      (node (ref "U15") (pin "11") (pinfunction "Y4_11") (pintype "passive"))
      (node (ref "U9") (pin "36") (pinfunction "IO3_36") (pintype "passive"))
    )
    (net (code "34") (name "/Interrupt0") (class "Default")
      (node (ref "Q2") (pin "1") (pinfunction "C_1") (pintype "passive"))
      (node (ref "R45") (pin "1") (pinfunction "1_1") (pintype "passive"))
    )
    (net (code "35") (name "/K1") (class "Default")
      (node (ref "R29") (pin "1") (pinfunction "1_1") (pintype "passive"))
      (node (ref "S5") (pin "2") (pinfunction "2_2") (pintype "passive"))
      (node (ref "U15") (pin "2") (pinfunction "A1_2") (pintype "passive"))
    )
    (net (code "36") (name "/K2") (class "Default")
      (node (ref "R30") (pin "1") (pinfunction "1_1") (pintype "passive"))
      (node (ref "S2") (pin "2") (pinfunction "2_2") (pintype "passive"))
      (node (ref "U15") (pin "5") (pinfunction "A2_5") (pintype "passive"))
    )
    (net (code "37") (name "/K3") (class "Default")
      (node (ref "R19") (pin "1") (pinfunction "1_1") (pintype "passive"))
      (node (ref "S3") (pin "2") (pinfunction "2_2") (pintype "passive"))
      (node (ref "U15") (pin "9") (pinfunction "A3_9") (pintype "passive"))
    )
    (net (code "38") (name "/K4") (class "Default")
      (node (ref "R20") (pin "2") (pinfunction "2_2") (pintype "passive"))
      (node (ref "S4") (pin "2") (pinfunction "2_2") (pintype "passive"))
      (node (ref "U15") (pin "12") (pinfunction "A4_12") (pintype "passive"))
    )
    (net (code "39") (name "/O0") (class "Default")
      (node (ref "P6") (pin "1") (pinfunction "1_1") (pintype "passive"))
      (node (ref "R21") (pin "1") (pinfunction "1_1") (pintype "passive"))
      (node (ref "U11") (pin "14") (pinfunction "Q0_14") (pintype "output"))
    )
    (net (code "40") (name "/O1") (class "Default")
      (node (ref "P6") (pin "2") (pinfunction "2_2") (pintype "passive"))
      (node (ref "R22") (pin "1") (pinfunction "1_1") (pintype "passive"))
      (node (ref "U11") (pin "13") (pinfunction "Q1_13") (pintype "output"))
    )
    (net (code "41") (name "/O2") (class "Default")
      (node (ref "P6") (pin "3") (pinfunction "3_3") (pintype "passive"))
      (node (ref "R23") (pin "1") (pinfunction "1_1") (pintype "passive"))
      (node (ref "U11") (pin "12") (pinfunction "Q2_12") (pintype "output"))
    )
    (net (code "42") (name "/O3") (class "Default")
      (node (ref "P6") (pin "4") (pinfunction "4_4") (pintype "passive"))
      (node (ref "R24") (pin "1") (pinfunction "1_1") (pintype "passive"))
      (node (ref "U11") (pin "11") (pinfunction "Q3_11") (pintype "output"))
    )
    (net (code "43") (name "/O4") (class "Default")
      (node (ref "P6") (pin "5") (pinfunction "5_5") (pintype "passive"))
      (node (ref "R25") (pin "1") (pinfunction "1_1") (pintype "passive"))
      (node (ref "U13") (pin "14") (pinfunction "Q0_14") (pintype "output"))
    )
    (net (code "44") (name "/O5") (class "Default")
      (node (ref "P6") (pin "6") (pinfunction "6_6") (pintype "passive"))
      (node (ref "R26") (pin "1") (pinfunction "1_1") (pintype "passive"))
      (node (ref "U13") (pin "13") (pinfunction "Q1_13") (pintype "output"))
    )
    (net (code "45") (name "/O6") (class "Default")
      (node (ref "P6") (pin "7") (pinfunction "7_7") (pintype "passive"))
      (node (ref "R27") (pin "1") (pinfunction "1_1") (pintype "passive"))
      (node (ref "U13") (pin "12") (pinfunction "Q2_12") (pintype "output"))
    )
    (net (code "46") (name "/O7") (class "Default")
      (node (ref "P6") (pin "8") (pinfunction "8_8") (pintype "passive"))
      (node (ref "R28") (pin "1") (pinfunction "1_1") (pintype "passive"))
      (node (ref "U13") (pin "11") (pinfunction "Q3_11") (pintype "output"))
    )
    (net (code "47") (name "/OUT0") (class "Default")
      (node (ref "P3") (pin "1") (pinfunction "1_1") (pintype "passive"))
      (node (ref "U11") (pin "2") (pinfunction "CLK_2") (pintype "input"))
      (node (ref "U16") (pin "15") (pinfunction "~{Y}0_15") (pintype "output"))
    )
    (net (code "48") (name "/OUT1") (class "Default")
      (node (ref "P3") (pin "2") (pinfunction "2_2") (pintype "passive"))
      (node (ref "U13") (pin "2") (pinfunction "CLK_2") (pintype "input"))
      (node (ref "U16") (pin "14") (pinfunction "~{Y}1_14") (pintype "output"))
    )
    (net (code "49") (name "/OUT2") (class "Default")
      (node (ref "P3") (pin "3") (pinfunction "3_3") (pintype "passive"))
      (node (ref "U16") (pin "13") (pinfunction "~{Y}2_13") (pintype "output"))
    )
    (net (code "50") (name "/OUT3") (class "Default")
      (node (ref "P3") (pin "4") (pinfunction "4_4") (pintype "passive"))
      (node (ref "U16") (pin "12") (pinfunction "~{Y}3_12") (pintype "output"))
    )
    (net (code "51") (name "/OUT4") (class "Default")
      (node (ref "P3") (pin "5") (pinfunction "5_5") (pintype "passive"))
      (node (ref "U16") (pin "11") (pinfunction "~{Y}4_11") (pintype "output"))
    )
    (net (code "52") (name "/OUT5") (class "Default")
      (node (ref "P3") (pin "6") (pinfunction "6_6") (pintype "passive"))
      (node (ref "U16") (pin "10") (pinfunction "~{Y}5_10") (pintype "output"))
    )
    (net (code "53") (name "/OUT6") (class "Default")
      (node (ref "P3") (pin "7") (pinfunction "7_7") (pintype "passive"))
      (node (ref "U16") (pin "9") (pinfunction "~{Y}6_9") (pintype "output"))
    )
    (net (code "54") (name "/OUT7") (class "Default")
      (node (ref "P3") (pin "8") (pinfunction "8_8") (pintype "passive"))
      (node (ref "U16") (pin "7") (pinfunction "~{Y}7_7") (pintype "output"))
    )
    (net (code "55") (name "/RESET") (class "Default")
      (node (ref "R38") (pin "1") (pinfunction "1_1") (pintype "passive"))
      (node (ref "R50") (pin "2") (pinfunction "2_2") (pintype "passive"))
      (node (ref "U1") (pin "7") (pinfunction "OUTB_7") (pintype "output"))
      (node (ref "U6") (pin "9") (pinfunction "RST_9") (pintype "passive"))
      (node (ref "U7") (pin "9") (pinfunction "RST_9") (pintype "passive"))
      (node (ref "U8") (pin "12") (pinfunction "RST_12") (pintype "passive"))
      (node (ref "U9") (pin "17") (pinfunction "RST_17") (pintype "passive"))
    )
    (net (code "56") (name "/SYNC") (class "Default")
      (node (ref "U6") (pin "8") (pinfunction "SYNC_8") (pintype "passive"))
      (node (ref "U7") (pin "8") (pinfunction "SYNC_8") (pintype "passive"))
      (node (ref "U8") (pin "16") (pinfunction "SYNC_16") (pintype "passive"))
      (node (ref "U9") (pin "15") (pinfunction "SYNC_15") (pintype "passive"))
    )
    (net (code "57") (name "/TEST") (class "Default")
      (node (ref "P5") (pin "2") (pinfunction "2_2") (pintype "passive"))
      (node (ref "R40") (pin "2") (pinfunction "2_2") (pintype "passive"))
      (node (ref "R42") (pin "1") (pinfunction "1_1") (pintype "passive"))
    )
    (net (code "58") (name "/Test0") (class "Default")
      (node (ref "Q3") (pin "1") (pinfunction "C_1") (pintype "passive"))
      (node (ref "R46") (pin "1") (pinfunction "1_1") (pintype "passive"))
      (node (ref "U7") (pin "10") (pinfunction "TEST_10") (pintype "passive"))
      (node (ref "U8") (pin "13") (pinfunction "TEST_13") (pintype "passive"))
    )
    (net (code "59") (name "GND") (class "Default")
      (node (ref "C1") (pin "1") (pinfunction "1_1") (pintype "passive"))
      (node (ref "C10") (pin "2") (pinfunction "2_2") (pintype "passive"))
      (node (ref "C11") (pin "1") (pinfunction "1_1") (pintype "passive"))
      (node (ref "C16") (pin "1") (pinfunction "1_1") (pintype "passive"))
      (node (ref "C18") (pin "1") (pinfunction "1_1") (pintype "passive"))
      (node (ref "C19") (pin "1") (pinfunction "1_1") (pintype "passive"))
      (node (ref "C2") (pin "1") (pinfunction "1_1") (pintype "passive"))
      (node (ref "C21") (pin "1") (pinfunction "1_1") (pintype "passive"))
      (node (ref "C3") (pin "1") (pinfunction "1_1") (pintype "passive"))
      (node (ref "C4") (pin "1") (pinfunction "1_1") (pintype "passive"))
      (node (ref "C6") (pin "1") (pinfunction "1_1") (pintype "passive"))
      (node (ref "C7") (pin "1") (pinfunction "1_1") (pintype "passive"))
      (node (ref "C8") (pin "1") (pinfunction "1_1") (pintype "passive"))
      (node (ref "C9") (pin "1") (pinfunction "1_1") (pintype "passive"))
      (node (ref "D1") (pin "2") (pinfunction "K_2") (pintype "passive"))
      (node (ref "D4") (pin "2") (pinfunction "K_2") (pintype "passive"))
      (node (ref "D5") (pin "2") (pinfunction "K_2") (pintype "passive"))
      (node (ref "D6") (pin "2") (pinfunction "K_2") (pintype "passive"))
      (node (ref "D7") (pin "2") (pinfunction "K_2") (pintype "passive"))
      (node (ref "J3") (pin "5") (pinfunction "GND_5") (pintype "passive"))
      (node (ref "J3") (pin "6") (pinfunction "Shell_6") (pintype "passive"))
      (node (ref "J3") (pin "7") (pinfunction "Shell_7") (pintype "passive"))
      (node (ref "J3") (pin "8") (pinfunction "Shell_8") (pintype "passive"))
      (node (ref "J3") (pin "9") (pinfunction "Shell_9") (pintype "passive"))
      (node (ref "P4") (pin "3") (pinfunction "3_3") (pintype "passive"))
      (node (ref "P4") (pin "4") (pinfunction "4_4") (pintype "passive"))
      (node (ref "Q2") (pin "3") (pinfunction "E_3") (pintype "passive"))
      (node (ref "Q3") (pin "3") (pinfunction "E_3") (pintype "passive"))
      (node (ref "R11") (pin "1") (pinfunction "1_1") (pintype "passive"))
      (node (ref "R12") (pin "1") (pinfunction "1_1") (pintype "passive"))
      (node (ref "R19") (pin "2") (pinfunction "2_2") (pintype "passive"))
      (node (ref "R20") (pin "1") (pinfunction "1_1") (pintype "passive"))
      (node (ref "R29") (pin "2") (pinfunction "2_2") (pintype "passive"))
      (node (ref "R30") (pin "2") (pinfunction "2_2") (pintype "passive"))
      (node (ref "R33") (pin "1") (pinfunction "1_1") (pintype "passive"))
      (node (ref "R39") (pin "1") (pinfunction "1_1") (pintype "passive"))
      (node (ref "R40") (pin "1") (pinfunction "1_1") (pintype "passive"))
      (node (ref "R6") (pin "1") (pinfunction "1_1") (pintype "passive"))
      (node (ref "R8") (pin "1") (pinfunction "1_1") (pintype "passive"))
      (node (ref "U1") (pin "6") (pinfunction "INB-_6") (pintype "input"))
      (node (ref "U10") (pin "8") (pinfunction "GND_8") (pintype "power_in"))
      (node (ref "U11") (pin "8") (pinfunction "GND_8") (pintype "power_in"))
      (node (ref "U11") (pin "9") (pinfunction "~{PE}_9") (pintype "input"))
      (node (ref "U13") (pin "8") (pinfunction "GND_8") (pintype "power_in"))
      (node (ref "U13") (pin "9") (pinfunction "~{PE}_9") (pintype "input"))
      (node (ref "U14") (pin "4") (pinfunction "GND_4") (pintype "power_in"))
      (node (ref "U15") (pin "7") (pinfunction "GND_7") (pintype "passive"))
      (node (ref "U16") (pin "8") (pinfunction "GND_8") (pintype "power_in"))
      (node (ref "U2") (pin "7") (pinfunction "GND_7") (pintype "power_in"))
      (node (ref "U3") (pin "10") (pinfunction "B_10") (pintype "input"))
      (node (ref "U3") (pin "7") (pinfunction "GND_7") (pintype "power_in"))
      (node (ref "U3") (pin "9") (pinfunction "A_9") (pintype "input"))
      (node (ref "U4") (pin "7") (pinfunction "GND_7") (pintype "power_in"))
      (node (ref "U5") (pin "14") (pinfunction "GND_14") (pintype "power_in"))
      (node (ref "U5") (pin "20") (pinfunction "~{CE}_20") (pintype "input"))
      (node (ref "U5") (pin "22") (pinfunction "~{OE}_22") (pintype "input"))
      (node (ref "U9") (pin "35") (pinfunction "GND_35") (pintype "passive"))
      (node (ref "X1") (pin "2") (pinfunction "GND_2") (pintype "passive"))
    )
    (net (code "60") (name "Net-(C14-Pad1)") (class "Default")
      (node (ref "C14") (pin "1") (pinfunction "1_1") (pintype "passive"))
      (node (ref "R4") (pin "2") (pinfunction "2_2") (pintype "passive"))
      (node (ref "R5") (pin "1") (pinfunction "1_1") (pintype "passive"))
    )
    (net (code "61") (name "Net-(C23-Pad1)") (class "Default")
      (node (ref "C23") (pin "1") (pinfunction "1_1") (pintype "passive"))
      (node (ref "R10") (pin "2") (pinfunction "2_2") (pintype "passive"))
      (node (ref "R9") (pin "1") (pinfunction "1_1") (pintype "passive"))
    )
    (net (code "62") (name "Net-(D1-A)") (class "Default")
      (node (ref "C15") (pin "2") (pinfunction "2_2") (pintype "passive"))
      (node (ref "D1") (pin "1") (pinfunction "A_1") (pintype "passive"))
      (node (ref "L2") (pin "1") (pinfunction "1_1") (pintype "passive"))
    )
    (net (code "63") (name "Net-(D2-A)") (class "Default")
      (node (ref "C16") (pin "2") (pinfunction "2_2") (pintype "passive"))
      (node (ref "D2") (pin "1") (pinfunction "A_1") (pintype "passive"))
      (node (ref "D3") (pin "2") (pinfunction "K_2") (pintype "passive"))
      (node (ref "U14") (pin "3") (pinfunction "INA+_3") (pintype "input"))
    )
    (net (code "64") (name "Net-(D3-A)") (class "Default")
      (node (ref "D3") (pin "1") (pinfunction "A_1") (pintype "passive"))
      (node (ref "R34") (pin "1") (pinfunction "1_1") (pintype "passive"))
      (node (ref "R35") (pin "1") (pinfunction "1_1") (pintype "passive"))
      (node (ref "U14") (pin "1") (pinfunction "OUTA_1") (pintype "output"))
      (node (ref "U14") (pin "6") (pinfunction "INB-_6") (pintype "input"))
    )
    (net (code "65") (name "Net-(D4-A)") (class "Default")
      (node (ref "D4") (pin "1") (pinfunction "A_1") (pintype "passive"))
      (node (ref "R13") (pin "2") (pinfunction "2_2") (pintype "passive"))
    )
    (net (code "66") (name "Net-(D5-A)") (class "Default")
      (node (ref "D5") (pin "1") (pinfunction "A_1") (pintype "passive"))
      (node (ref "R14") (pin "2") (pinfunction "2_2") (pintype "passive"))
    )
    (net (code "67") (name "Net-(D6-A)") (class "Default")
      (node (ref "D6") (pin "1") (pinfunction "A_1") (pintype "passive"))
      (node (ref "R15") (pin "2") (pinfunction "2_2") (pintype "passive"))
    )
    (net (code "68") (name "Net-(D7-A)") (class "Default")
      (node (ref "D7") (pin "1") (pinfunction "A_1") (pintype "passive"))
      (node (ref "R16") (pin "2") (pinfunction "2_2") (pintype "passive"))
    )
    (net (code "69") (name "Net-(D8-A)") (class "Default")
      (node (ref "D8") (pin "1") (pinfunction "A_1") (pintype "passive"))
      (node (ref "R21") (pin "2") (pinfunction "2_2") (pintype "passive"))
    )
    (net (code "70") (name "Net-(D9-A)") (class "Default")
      (node (ref "D9") (pin "1") (pinfunction "A_1") (pintype "passive"))
      (node (ref "R22") (pin "2") (pinfunction "2_2") (pintype "passive"))
    )
    (net (code "71") (name "Net-(D10-A)") (class "Default")
      (node (ref "D10") (pin "1") (pinfunction "A_1") (pintype "passive"))
      (node (ref "R23") (pin "2") (pinfunction "2_2") (pintype "passive"))
    )
    (net (code "72") (name "Net-(D11-A)") (class "Default")
      (node (ref "D11") (pin "1") (pinfunction "A_1") (pintype "passive"))
      (node (ref "R24") (pin "2") (pinfunction "2_2") (pintype "passive"))
    )
    (net (code "73") (name "Net-(D12-A)") (class "Default")
      (node (ref "D12") (pin "1") (pinfunction "A_1") (pintype "passive"))
      (node (ref "R25") (pin "2") (pinfunction "2_2") (pintype "passive"))
    )
    (net (code "74") (name "Net-(D13-A)") (class "Default")
      (node (ref "D13") (pin "1") (pinfunction "A_1") (pintype "passive"))
      (node (ref "R26") (pin "2") (pinfunction "2_2") (pintype "passive"))
    )
    (net (code "75") (name "Net-(D14-A)") (class "Default")
      (node (ref "D14") (pin "1") (pinfunction "A_1") (pintype "passive"))
      (node (ref "R27") (pin "2") (pinfunction "2_2") (pintype "passive"))
    )
    (net (code "76") (name "Net-(D15-A)") (class "Default")
      (node (ref "D15") (pin "1") (pinfunction "A_1") (pintype "passive"))
      (node (ref "R28") (pin "2") (pinfunction "2_2") (pintype "passive"))
    )
    (net (code "77") (name "Net-(D17-A)") (class "Default")
      (node (ref "C17") (pin "2") (pinfunction "2_2") (pintype "passive"))
      (node (ref "D17") (pin "1") (pinfunction "A_1") (pintype "passive"))
      (node (ref "R1") (pin "1") (pinfunction "1_1") (pintype "passive"))
      (node (ref "R31") (pin "1") (pinfunction "1_1") (pintype "passive"))
    )
    (net (code "78") (name "Net-(D18-A)") (class "Default")
      (node (ref "C5") (pin "2") (pinfunction "2_2") (pintype "passive"))
      (node (ref "D18") (pin "1") (pinfunction "A_1") (pintype "passive"))
      (node (ref "R2") (pin "2") (pinfunction "2_2") (pintype "passive"))
      (node (ref "U12") (pin "4") (pinfunction "~{SHDN}_4") (pintype "input"))
    )
    (net (code "79") (name "Net-(D19-A)") (class "Default")
      (node (ref "D19") (pin "1") (pinfunction "A_1") (pintype "passive"))
      (node (ref "R43") (pin "1") (pinfunction "1_1") (pintype "passive"))
    )
    (net (code "80") (name "Net-(D19-K)") (class "Default")
      (node (ref "D19") (pin "2") (pinfunction "K_2") (pintype "passive"))
      (node (ref "U14") (pin "7") (pinfunction "OUTB_7") (pintype "output"))
    )
    (net (code "81") (name "Net-(J1-C2)") (class "Default")
      (node (ref "J1") (pin "2") (pinfunction "C2_2") (pintype "passive"))
      (node (ref "U5") (pin "23") (pinfunction "A11_23") (pintype "input"))
      (node (ref "W2") (pin "2") (pinfunction "C2_2") (pintype "passive"))
    )
    (net (code "82") (name "Net-(J3-Vcc)") (class "Default")
      (node (ref "J3") (pin "1") (pinfunction "Vcc_1") (pintype "passive"))
      (node (ref "S7") (pin "2") (pinfunction "NO_2") (pintype "passive"))
    )
    (net (code "83") (name "Net-(Q1-B)") (class "Default")
      (node (ref "Q1") (pin "2") (pinfunction "B_2") (pintype "passive"))
      (node (ref "R35") (pin "2") (pinfunction "2_2") (pintype "passive"))
    )
    (net (code "84") (name "Net-(Q1-E)") (class "Default")
      (node (ref "Q1") (pin "3") (pinfunction "E_3") (pintype "passive"))
      (node (ref "R17") (pin "2") (pinfunction "2_2") (pintype "passive"))
      (node (ref "R18") (pin "2") (pinfunction "2_2") (pintype "passive"))
    )
    (net (code "85") (name "Net-(Q2-B)") (class "Default")
      (node (ref "Q2") (pin "2") (pinfunction "B_2") (pintype "passive"))
      (node (ref "R41") (pin "2") (pinfunction "2_2") (pintype "passive"))
    )
    (net (code "86") (name "Net-(Q3-B)") (class "Default")
      (node (ref "Q3") (pin "2") (pinfunction "B_2") (pintype "passive"))
      (node (ref "R42") (pin "2") (pinfunction "2_2") (pintype "passive"))
    )
    (net (code "87") (name "Net-(R3-Pad1)") (class "Default")
      (node (ref "R3") (pin "1") (pinfunction "1_1") (pintype "passive"))
      (node (ref "R8") (pin "2") (pinfunction "2_2") (pintype "passive"))
    )
    (net (code "88") (name "Net-(S1-B1)") (class "Default")
      (node (ref "R12") (pin "2") (pinfunction "2_2") (pintype "passive"))
      (node (ref "S1") (pin "4") (pinfunction "B1_4") (pintype "passive"))
      (node (ref "W2") (pin "1") (pinfunction "C1_1") (pintype "passive"))
    )
    (net (code "89") (name "Net-(S1-B2)") (class "Default")
      (node (ref "R11") (pin "2") (pinfunction "2_2") (pintype "passive"))
      (node (ref "S1") (pin "3") (pinfunction "B2_3") (pintype "passive"))
      (node (ref "U5") (pin "2") (pinfunction "A12_2") (pintype "input"))
    )
    (net (code "90") (name "Net-(S7-COMMON)") (class "Default")
      (node (ref "F1") (pin "2") (pinfunction "2_2") (pintype "passive"))
      (node (ref "S7") (pin "1") (pinfunction "COMMON_1") (pintype "passive"))
    )
    (net (code "91") (name "Net-(U1B-INB+)") (class "Default")
      (node (ref "R1") (pin "2") (pinfunction "2_2") (pintype "passive"))
      (node (ref "R50") (pin "1") (pinfunction "1_1") (pintype "passive"))
      (node (ref "S6") (pin "1") (pinfunction "1_1") (pintype "passive"))
      (node (ref "U1") (pin "5") (pinfunction "INB+_5") (pintype "input"))
    )
    (net (code "92") (name "Net-(U2A-D)") (class "Default")
      (node (ref "U2") (pin "11") (pinfunction "CLK_11") (pintype "input"))
      (node (ref "U2") (pin "2") (pinfunction "D_2") (pintype "input"))
      (node (ref "U4") (pin "11") (pinfunction "CLK_11") (pintype "input"))
      (node (ref "U4") (pin "6") (pinfunction "~{Q}_6") (pintype "output"))
    )
    (net (code "93") (name "Net-(U2A-Q)") (class "Default")
      (node (ref "U2") (pin "5") (pinfunction "Q_5") (pintype "output"))
      (node (ref "U4") (pin "2") (pinfunction "D_2") (pintype "input"))
    )
    (net (code "94") (name "Net-(U2B-D)") (class "Default")
      (node (ref "U2") (pin "12") (pinfunction "D_12") (pintype "input"))
      (node (ref "U3") (pin "4") (pinfunction "A_4") (pintype "input"))
      (node (ref "U4") (pin "8") (pinfunction "~{Q}_8") (pintype "output"))
    )
    (net (code "95") (name "Net-(U2B-Q)") (class "Default")
      (node (ref "U2") (pin "9") (pinfunction "Q_9") (pintype "output"))
      (node (ref "U3") (pin "2") (pinfunction "B_2") (pintype "input"))
      (node (ref "U4") (pin "12") (pinfunction "D_12") (pintype "input"))
    )
    (net (code "96") (name "Net-(U2B-~{Q})") (class "Default")
      (node (ref "U2") (pin "8") (pinfunction "~{Q}_8") (pintype "output"))
      (node (ref "U3") (pin "5") (pinfunction "B_5") (pintype "input"))
    )
    (net (code "97") (name "Net-(U3A-A)") (class "Default")
      (node (ref "U3") (pin "1") (pinfunction "A_1") (pintype "input"))
      (node (ref "U4") (pin "9") (pinfunction "Q_9") (pintype "output"))
    )
    (net (code "98") (name "Net-(U5-DQ0)") (class "Default")
      (node (ref "U5") (pin "11") (pinfunction "DQ0_11") (pintype "bidirectional"))
      (node (ref "U9") (pin "9") (pinfunction "M0_9") (pintype "passive"))
    )
    (net (code "99") (name "Net-(U5-DQ1)") (class "Default")
      (node (ref "U5") (pin "12") (pinfunction "DQ1_12") (pintype "bidirectional"))
      (node (ref "U9") (pin "10") (pinfunction "M1_10") (pintype "passive"))
    )
    (net (code "100") (name "Net-(U5-DQ2)") (class "Default")
      (node (ref "U5") (pin "13") (pinfunction "DQ2_13") (pintype "bidirectional"))
      (node (ref "U9") (pin "11") (pinfunction "M2_11") (pintype "passive"))
    )
    (net (code "101") (name "Net-(U5-DQ3)") (class "Default")
      (node (ref "U5") (pin "15") (pinfunction "DQ3_15") (pintype "bidirectional"))
      (node (ref "U9") (pin "12") (pinfunction "M3_12") (pintype "passive"))
    )
    (net (code "102") (name "Net-(U5-DQ4)") (class "Default")
      (node (ref "U5") (pin "16") (pinfunction "DQ4_16") (pintype "bidirectional"))
      (node (ref "U9") (pin "5") (pinfunction "M4_5") (pintype "passive"))
    )
    (net (code "103") (name "Net-(U5-DQ5)") (class "Default")
      (node (ref "U5") (pin "17") (pinfunction "DQ5_17") (pintype "bidirectional"))
      (node (ref "U9") (pin "6") (pinfunction "M5_6") (pintype "passive"))
    )
    (net (code "104") (name "Net-(U5-DQ6)") (class "Default")
      (node (ref "U5") (pin "18") (pinfunction "DQ6_18") (pintype "bidirectional"))
      (node (ref "U9") (pin "7") (pinfunction "M6_7") (pintype "passive"))
    )
    (net (code "105") (name "Net-(U5-DQ7)") (class "Default")
      (node (ref "U5") (pin "19") (pinfunction "DQ7_19") (pintype "bidirectional"))
      (node (ref "U9") (pin "8") (pinfunction "M7_8") (pintype "passive"))
    )
    (net (code "106") (name "Net-(U6-CM)") (class "Default")
      (node (ref "U6") (pin "11") (pinfunction "CM_11") (pintype "passive"))
      (node (ref "U7") (pin "16") (pinfunction "CMRAM0_16") (pintype "passive"))
      (node (ref "U8") (pin "20") (pinfunction "CMRAM0_20") (pintype "passive"))
    )
    (net (code "107") (name "Net-(U6-D0)") (class "Default")
      (node (ref "U6") (pin "1") (pinfunction "D0_1") (pintype "passive"))
      (node (ref "U7") (pin "1") (pinfunction "D0_1") (pintype "passive"))
      (node (ref "U8") (pin "1") (pinfunction "D0_1") (pintype "passive"))
      (node (ref "U9") (pin "1") (pinfunction "D0_1") (pintype "passive"))
    )
    (net (code "108") (name "Net-(U6-D1)") (class "Default")
      (node (ref "U6") (pin "2") (pinfunction "D1_2") (pintype "passive"))
      (node (ref "U7") (pin "2") (pinfunction "D1_2") (pintype "passive"))
      (node (ref "U8") (pin "2") (pinfunction "D1_2") (pintype "passive"))
      (node (ref "U9") (pin "2") (pinfunction "D1_2") (pintype "passive"))
    )
    (net (code "109") (name "Net-(U6-D2)") (class "Default")
      (node (ref "U6") (pin "3") (pinfunction "D2_3") (pintype "passive"))
      (node (ref "U7") (pin "3") (pinfunction "D2_3") (pintype "passive"))
      (node (ref "U8") (pin "3") (pinfunction "D2_3") (pintype "passive"))
      (node (ref "U9") (pin "3") (pinfunction "D2_3") (pintype "passive"))
    )
    (net (code "110") (name "Net-(U6-D3)") (class "Default")
      (node (ref "U6") (pin "4") (pinfunction "D3_4") (pintype "passive"))
      (node (ref "U7") (pin "4") (pinfunction "D3_4") (pintype "passive"))
      (node (ref "U8") (pin "4") (pinfunction "D3_4") (pintype "passive"))
      (node (ref "U9") (pin "4") (pinfunction "D3_4") (pintype "passive"))
    )
    (net (code "111") (name "Net-(U6-O0)") (class "Default")
      (node (ref "R13") (pin "1") (pinfunction "1_1") (pintype "passive"))
      (node (ref "U6") (pin "16") (pinfunction "O0_16") (pintype "passive"))
    )
    (net (code "112") (name "Net-(U6-O1)") (class "Default")
      (node (ref "R14") (pin "1") (pinfunction "1_1") (pintype "passive"))
      (node (ref "U6") (pin "15") (pinfunction "O1_15") (pintype "passive"))
    )
    (net (code "113") (name "Net-(U6-O2)") (class "Default")
      (node (ref "R15") (pin "1") (pinfunction "1_1") (pintype "passive"))
      (node (ref "U6") (pin "14") (pinfunction "O2_14") (pintype "passive"))
    )
    (net (code "114") (name "Net-(U6-O3)") (class "Default")
      (node (ref "R16") (pin "1") (pinfunction "1_1") (pintype "passive"))
      (node (ref "U6") (pin "13") (pinfunction "O3_13") (pintype "passive"))
    )
    (net (code "115") (name "Net-(U7-CMROM)") (class "Default")
      (node (ref "U7") (pin "11") (pinfunction "CMROM_11") (pintype "passive"))
      (node (ref "U8") (pin "23") (pinfunction "CMROM0_23") (pintype "passive"))
      (node (ref "U9") (pin "16") (pinfunction "CM_16") (pintype "passive"))
    )
    (net (code "116") (name "Net-(U12-NFB)") (class "Default")
      (node (ref "R6") (pin "2") (pinfunction "2_2") (pintype "passive"))
      (node (ref "R7") (pin "1") (pinfunction "1_1") (pintype "passive"))
      (node (ref "U12") (pin "3") (pinfunction "NFB_3") (pintype "input"))
    )
    (net (code "117") (name "Net-(U12-SW)") (class "Default")
      (node (ref "C15") (pin "1") (pinfunction "1_1") (pintype "passive"))
      (node (ref "L1") (pin "2") (pinfunction "2_2") (pintype "passive"))
      (node (ref "U12") (pin "1") (pinfunction "SW_1") (pintype "passive"))
    )
    (net (code "118") (name "Net-(U14A-INA-)") (class "Default")
      (node (ref "R18") (pin "1") (pinfunction "1_1") (pintype "passive"))
      (node (ref "R33") (pin "2") (pinfunction "2_2") (pintype "passive"))
      (node (ref "U14") (pin "2") (pinfunction "INA-_2") (pintype "input"))
      (node (ref "U14") (pin "5") (pinfunction "INB+_5") (pintype "input"))
    )
    (net (code "119") (name "Net-(U17-INA)") (class "Default")
      (node (ref "R10") (pin "1") (pinfunction "1_1") (pintype "passive"))
      (node (ref "U17") (pin "2") (pinfunction "INA_2") (pintype "input"))
    )
    (net (code "120") (name "Net-(U17-INB)") (class "Default")
      (node (ref "R5") (pin "2") (pinfunction "2_2") (pintype "passive"))
      (node (ref "U17") (pin "4") (pinfunction "INB_4") (pintype "input"))
    )
    (net (code "121") (name "Net-(U17-~{OUTA})") (class "Default")
      (node (ref "R36") (pin "1") (pinfunction "1_1") (pintype "passive"))
      (node (ref "U17") (pin "7") (pinfunction "~{OUTA}_7") (pintype "output"))
    )
    (net (code "122") (name "Net-(U17-~{OUTB})") (class "Default")
      (node (ref "R37") (pin "2") (pinfunction "2_2") (pintype "passive"))
      (node (ref "U17") (pin "5") (pinfunction "~{OUTB}_5") (pintype "output"))
    )
    (net (code "123") (name "VCC") (class "Default")
      (node (ref "C1") (pin "2") (pinfunction "2_2") (pintype "passive"))
      (node (ref "C11") (pin "2") (pinfunction "2_2") (pintype "passive"))
      (node (ref "C12") (pin "2") (pinfunction "2_2") (pintype "passive"))
      (node (ref "C13") (pin "2") (pinfunction "2_2") (pintype "passive"))
      (node (ref "C18") (pin "2") (pinfunction "2_2") (pintype "passive"))
      (node (ref "C2") (pin "2") (pinfunction "2_2") (pintype "passive"))
      (node (ref "C20") (pin "2") (pinfunction "2_2") (pintype "passive"))
      (node (ref "C22") (pin "2") (pinfunction "2_2") (pintype "passive"))
      (node (ref "C24") (pin "2") (pinfunction "2_2") (pintype "passive"))
      (node (ref "C3") (pin "2") (pinfunction "2_2") (pintype "passive"))
      (node (ref "C4") (pin "2") (pinfunction "2_2") (pintype "passive"))
      (node (ref "C6") (pin "2") (pinfunction "2_2") (pintype "passive"))
      (node (ref "C7") (pin "2") (pinfunction "2_2") (pintype "passive"))
      (node (ref "C8") (pin "2") (pinfunction "2_2") (pintype "passive"))
      (node (ref "C9") (pin "2") (pinfunction "2_2") (pintype "passive"))
      (node (ref "D17") (pin "2") (pinfunction "K_2") (pintype "passive"))
      (node (ref "D18") (pin "2") (pinfunction "K_2") (pintype "passive"))
      (node (ref "L1") (pin "1") (pinfunction "1_1") (pintype "passive"))
      (node (ref "Q1") (pin "1") (pinfunction "C_1") (pintype "passive"))
      (node (ref "R2") (pin "1") (pinfunction "1_1") (pintype "passive"))
      (node (ref "R31") (pin "2") (pinfunction "2_2") (pintype "passive"))
      (node (ref "R38") (pin "2") (pinfunction "2_2") (pintype "passive"))
      (node (ref "R45") (pin "2") (pinfunction "2_2") (pintype "passive"))
      (node (ref "R46") (pin "2") (pinfunction "2_2") (pintype "passive"))
      (node (ref "S1") (pin "1") (pinfunction "A1_1") (pintype "passive"))
      (node (ref "S1") (pin "2") (pinfunction "A2_2") (pintype "passive"))
      (node (ref "S2") (pin "1") (pinfunction "1_1") (pintype "passive"))
      (node (ref "S3") (pin "1") (pinfunction "1_1") (pintype "passive"))
      (node (ref "S4") (pin "1") (pinfunction "1_1") (pintype "passive"))
      (node (ref "S5") (pin "1") (pinfunction "1_1") (pintype "passive"))
      (node (ref "U1") (pin "2") (pinfunction "INA-_2") (pintype "input"))
      (node (ref "U1") (pin "8") (pinfunction "V+_8") (pintype "power_in"))
      (node (ref "U10") (pin "16") (pinfunction "VCC_16") (pintype "power_in"))
      (node (ref "U10") (pin "6") (pinfunction "OE1_6") (pintype "input"))
      (node (ref "U11") (pin "1") (pinfunction "~{RST}_1") (pintype "input"))
      (node (ref "U11") (pin "10") (pinfunction "CET_10") (pintype "input"))
      (node (ref "U11") (pin "16") (pinfunction "VCC_16") (pintype "power_in"))
      (node (ref "U11") (pin "7") (pinfunction "CEP_7") (pintype "input"))
      (node (ref "U12") (pin "5") (pinfunction "VIN_5") (pintype "power_in"))
      (node (ref "U13") (pin "1") (pinfunction "~{RST}_1") (pintype "input"))
      (node (ref "U13") (pin "10") (pinfunction "CET_10") (pintype "input"))
      (node (ref "U13") (pin "16") (pinfunction "VCC_16") (pintype "power_in"))
      (node (ref "U13") (pin "7") (pinfunction "CEP_7") (pintype "input"))
      (node (ref "U15") (pin "14") (pinfunction "VCC_14") (pintype "passive"))
      (node (ref "U16") (pin "16") (pinfunction "VCC_16") (pintype "power_in"))
      (node (ref "U16") (pin "6") (pinfunction "OE1_6") (pintype "input"))
      (node (ref "U17") (pin "6") (pinfunction "VCC_6") (pintype "power_in"))
      (node (ref "U2") (pin "1") (pinfunction "CLR_1") (pintype "input"))
      (node (ref "U2") (pin "10") (pinfunction "PR_10") (pintype "input"))
      (node (ref "U2") (pin "13") (pinfunction "CLR_13") (pintype "input"))
      (node (ref "U2") (pin "14") (pinfunction "VCC_14") (pintype "power_in"))
      (node (ref "U2") (pin "4") (pinfunction "PR_4") (pintype "input"))
      (node (ref "U3") (pin "12") (pinfunction "A_12") (pintype "input"))
      (node (ref "U3") (pin "13") (pinfunction "B_13") (pintype "input"))
      (node (ref "U3") (pin "14") (pinfunction "VCC_14") (pintype "power_in"))
      (node (ref "U4") (pin "1") (pinfunction "CLR_1") (pintype "input"))
      (node (ref "U4") (pin "10") (pinfunction "PR_10") (pintype "input"))
      (node (ref "U4") (pin "13") (pinfunction "CLR_13") (pintype "input"))
      (node (ref "U4") (pin "14") (pinfunction "VCC_14") (pintype "power_in"))
      (node (ref "U4") (pin "4") (pinfunction "PR_4") (pintype "input"))
      (node (ref "U5") (pin "27") (pinfunction "~{WE}_27") (pintype "input"))
      (node (ref "U5") (pin "28") (pinfunction "VCC_28") (pintype "power_in"))
      (node (ref "U7") (pin "5") (pinfunction "VSS(5)_5") (pintype "passive"))
      (node (ref "U8") (pin "9") (pinfunction "VSS(5)_9") (pintype "passive"))
      (node (ref "U9") (pin "20") (pinfunction "VSS(5)_20") (pintype "passive"))
      (node (ref "X1") (pin "4") (pinfunction "VCC_4") (pintype "passive"))
    )
    (net (code "124") (name "VCC IN") (class "Default")
      (node (ref "C19") (pin "2") (pinfunction "2_2") (pintype "passive"))
      (node (ref "D2") (pin "2") (pinfunction "K_2") (pintype "passive"))
      (node (ref "F1") (pin "1") (pinfunction "1_1") (pintype "passive"))
      (node (ref "P4") (pin "1") (pinfunction "1_1") (pintype "passive"))
      (node (ref "P4") (pin "2") (pinfunction "2_2") (pintype "passive"))
      (node (ref "R17") (pin "1") (pinfunction "1_1") (pintype "passive"))
      (node (ref "R3") (pin "2") (pinfunction "2_2") (pintype "passive"))
      (node (ref "R34") (pin "2") (pinfunction "2_2") (pintype "passive"))
      (node (ref "R43") (pin "2") (pinfunction "2_2") (pintype "passive"))
      (node (ref "U14") (pin "8") (pinfunction "V+_8") (pintype "power_in"))
    )
    (net (code "125") (name "unconnected-(C14-Pad2)") (class "Default")
      (node (ref "C14") (pin "2") (pinfunction "2_2") (pintype "passive"))
    )
    (net (code "126") (name "unconnected-(C23-Pad2)") (class "Default")
      (node (ref "C23") (pin "2") (pinfunction "2_2") (pintype "passive"))
    )
    (net (code "127") (name "unconnected-(D8-K-Pad2)") (class "Default")
      (node (ref "D8") (pin "2") (pinfunction "K_2") (pintype "passive"))
    )
    (net (code "128") (name "unconnected-(D9-K-Pad2)") (class "Default")
      (node (ref "D9") (pin "2") (pinfunction "K_2") (pintype "passive"))
    )
    (net (code "129") (name "unconnected-(D10-K-Pad2)") (class "Default")
      (node (ref "D10") (pin "2") (pinfunction "K_2") (pintype "passive"))
    )
    (net (code "130") (name "unconnected-(D11-K-Pad2)") (class "Default")
      (node (ref "D11") (pin "2") (pinfunction "K_2") (pintype "passive"))
    )
    (net (code "131") (name "unconnected-(D12-K-Pad2)") (class "Default")
      (node (ref "D12") (pin "2") (pinfunction "K_2") (pintype "passive"))
    )
    (net (code "132") (name "unconnected-(D13-K-Pad2)") (class "Default")
      (node (ref "D13") (pin "2") (pinfunction "K_2") (pintype "passive"))
    )
    (net (code "133") (name "unconnected-(D14-K-Pad2)") (class "Default")
      (node (ref "D14") (pin "2") (pinfunction "K_2") (pintype "passive"))
    )
    (net (code "134") (name "unconnected-(D15-K-Pad2)") (class "Default")
      (node (ref "D15") (pin "2") (pinfunction "K_2") (pintype "passive"))
    )
    (net (code "135") (name "unconnected-(J3-D+-Pad3)") (class "Default")
      (node (ref "J3") (pin "3") (pinfunction "D+_3") (pintype "passive"))
    )
    (net (code "136") (name "unconnected-(J3-D--Pad2)") (class "Default")
      (node (ref "J3") (pin "2") (pinfunction "D-_2") (pintype "passive"))
    )
    (net (code "137") (name "unconnected-(J3-NC-Pad4)") (class "Default")
      (node (ref "J3") (pin "4") (pinfunction "NC_4") (pintype "passive"))
    )
    (net (code "138") (name "unconnected-(U1A-OUTA-Pad1)") (class "Default")
      (node (ref "U1") (pin "1") (pinfunction "OUTA_1") (pintype "output"))
    )
    (net (code "139") (name "unconnected-(U2A-~{Q}-Pad6)") (class "Default")
      (node (ref "U2") (pin "6") (pinfunction "~{Q}_6") (pintype "output"))
    )
    (net (code "140") (name "unconnected-(U3A-Y-Pad3)") (class "Default")
      (node (ref "U3") (pin "3") (pinfunction "Y_3") (pintype "output"))
    )
    (net (code "141") (name "unconnected-(U3B-Y-Pad6)") (class "Default")
      (node (ref "U3") (pin "6") (pinfunction "Y_6") (pintype "output"))
    )
    (net (code "142") (name "unconnected-(U3C-Y-Pad8)") (class "Default")
      (node (ref "U3") (pin "8") (pinfunction "Y_8") (pintype "output"))
    )
    (net (code "143") (name "unconnected-(U3D-Y-Pad11)") (class "Default")
      (node (ref "U3") (pin "11") (pinfunction "Y_11") (pintype "output"))
    )
    (net (code "144") (name "unconnected-(U4A-Q-Pad5)") (class "Default")
      (node (ref "U4") (pin "5") (pinfunction "Q_5") (pintype "output"))
    )
    (net (code "145") (name "unconnected-(U5-NC-Pad26)") (class "Default")
      (node (ref "U5") (pin "26") (pinfunction "NC_26") (pintype "passive"))
    )
    (net (code "146") (name "unconnected-(U5-R~{B}-Pad1)") (class "Default")
      (node (ref "U5") (pin "1") (pinfunction "R~{B}_1") (pintype "passive"))
    )
    (net (code "147") (name "unconnected-(U6-P0-Pad10)") (class "Default")
      (node (ref "U6") (pin "10") (pinfunction "P0_10") (pintype "passive"))
    )
    (net (code "148") (name "unconnected-(U6-VDD(-10)-Pad12)") (class "Default")
      (node (ref "U6") (pin "12") (pinfunction "VDD(-10)_12") (pintype "passive"))
    )
    (net (code "149") (name "unconnected-(U6-VSS(5)-Pad5)") (class "Default")
      (node (ref "U6") (pin "5") (pinfunction "VSS(5)_5") (pintype "passive"))
    )
    (net (code "150") (name "unconnected-(U7-CMRAM1-Pad15)") (class "Default")
      (node (ref "U7") (pin "15") (pinfunction "CMRAM1_15") (pintype "passive"))
    )
    (net (code "151") (name "unconnected-(U7-CMRAM2-Pad14)") (class "Default")
      (node (ref "U7") (pin "14") (pinfunction "CMRAM2_14") (pintype "passive"))
    )
    (net (code "152") (name "unconnected-(U7-CMRAM3-Pad13)") (class "Default")
      (node (ref "U7") (pin "13") (pinfunction "CMRAM3_13") (pintype "passive"))
    )
    (net (code "153") (name "unconnected-(U8-CMRAM1-Pad19)") (class "Default")
      (node (ref "U8") (pin "19") (pinfunction "CMRAM1_19") (pintype "passive"))
    )
    (net (code "154") (name "unconnected-(U8-CMRAM2-Pad18)") (class "Default")
      (node (ref "U8") (pin "18") (pinfunction "CMRAM2_18") (pintype "passive"))
    )
    (net (code "155") (name "unconnected-(U8-CMRAM3-Pad17)") (class "Default")
      (node (ref "U8") (pin "17") (pinfunction "CMRAM3_17") (pintype "passive"))
    )
    (net (code "156") (name "unconnected-(U8-CMROM1-Pad22)") (class "Default")
      (node (ref "U8") (pin "22") (pinfunction "CMROM1_22") (pintype "passive"))
    )
    (net (code "157") (name "unconnected-(U8-STOP-Pad6)") (class "Default")
      (node (ref "U8") (pin "6") (pinfunction "STOP_6") (pintype "passive"))
    )
    (net (code "158") (name "unconnected-(U8-STOP_ACT-Pad5)") (class "Default")
      (node (ref "U8") (pin "5") (pinfunction "STOP_ACT_5") (pintype "passive"))
    )
    (net (code "159") (name "unconnected-(U9-F{slash}L-Pad22)") (class "Default")
      (node (ref "U9") (pin "22") (pinfunction "F/L_22") (pintype "passive"))
    )
    (net (code "160") (name "unconnected-(U9-W-Pad21)") (class "Default")
      (node (ref "U9") (pin "21") (pinfunction "W_21") (pintype "passive"))
    )
    (net (code "161") (name "unconnected-(U11-TC-Pad15)") (class "Default")
      (node (ref "U11") (pin "15") (pinfunction "TC_15") (pintype "output"))
    )
    (net (code "162") (name "unconnected-(U12-GND-Pad2)") (class "Default")
      (node (ref "U12") (pin "2") (pinfunction "GND_2") (pintype "power_in"))
    )
    (net (code "163") (name "unconnected-(U13-TC-Pad15)") (class "Default")
      (node (ref "U13") (pin "15") (pinfunction "TC_15") (pintype "output"))
    )
    (net (code "164") (name "unconnected-(U17-NC-Pad1)") (class "Default")
      (node (ref "U17") (pin "1") (pinfunction "NC_1") (pintype "passive"))
    )
    (net (code "165") (name "unconnected-(U17-NC-Pad8)") (class "Default")
      (node (ref "U17") (pin "8") (pinfunction "NC_8") (pintype "passive"))
    )
    (net (code "166") (name "unconnected-(X1-NC-Pad1)") (class "Default")
      (node (ref "X1") (pin "1") (pinfunction "NC_1") (pintype "passive"))
    )
  )
)
